# NHK2016mother_rev4.net
KiCad netlist of a schematic drawn in EAGLE
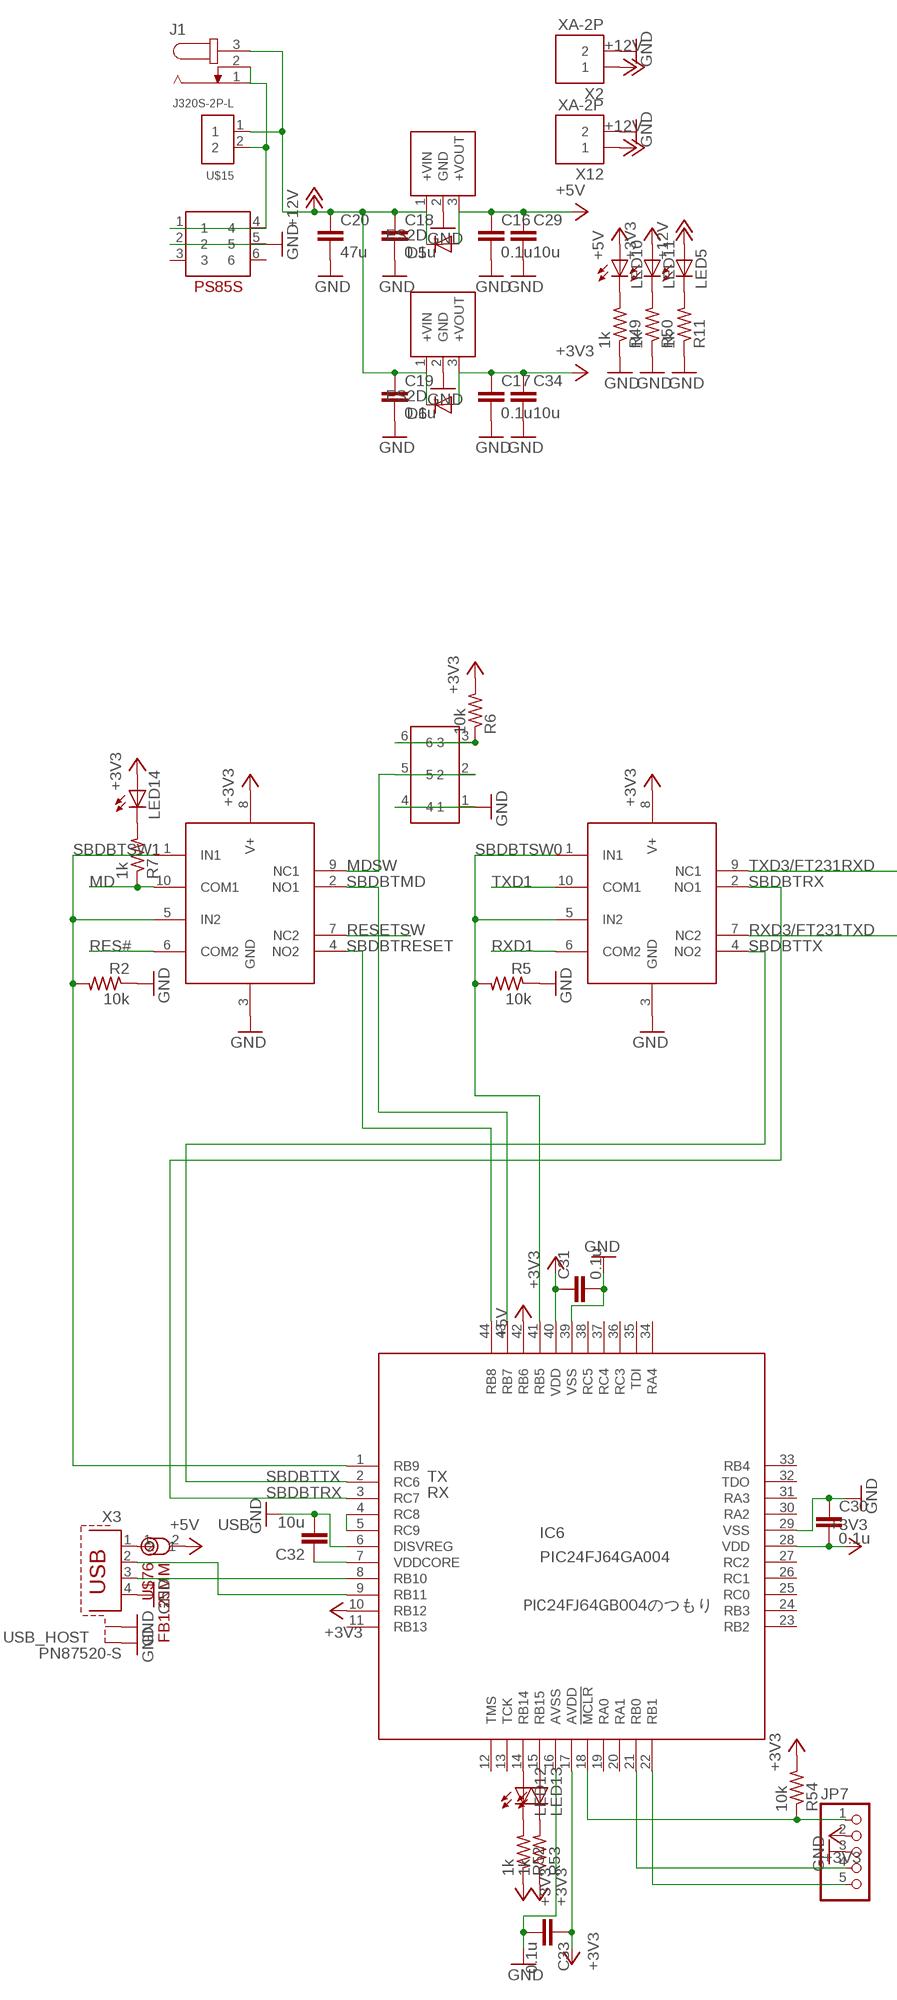
[diagram p0: schematic, sheet 1, part 1 of 2]
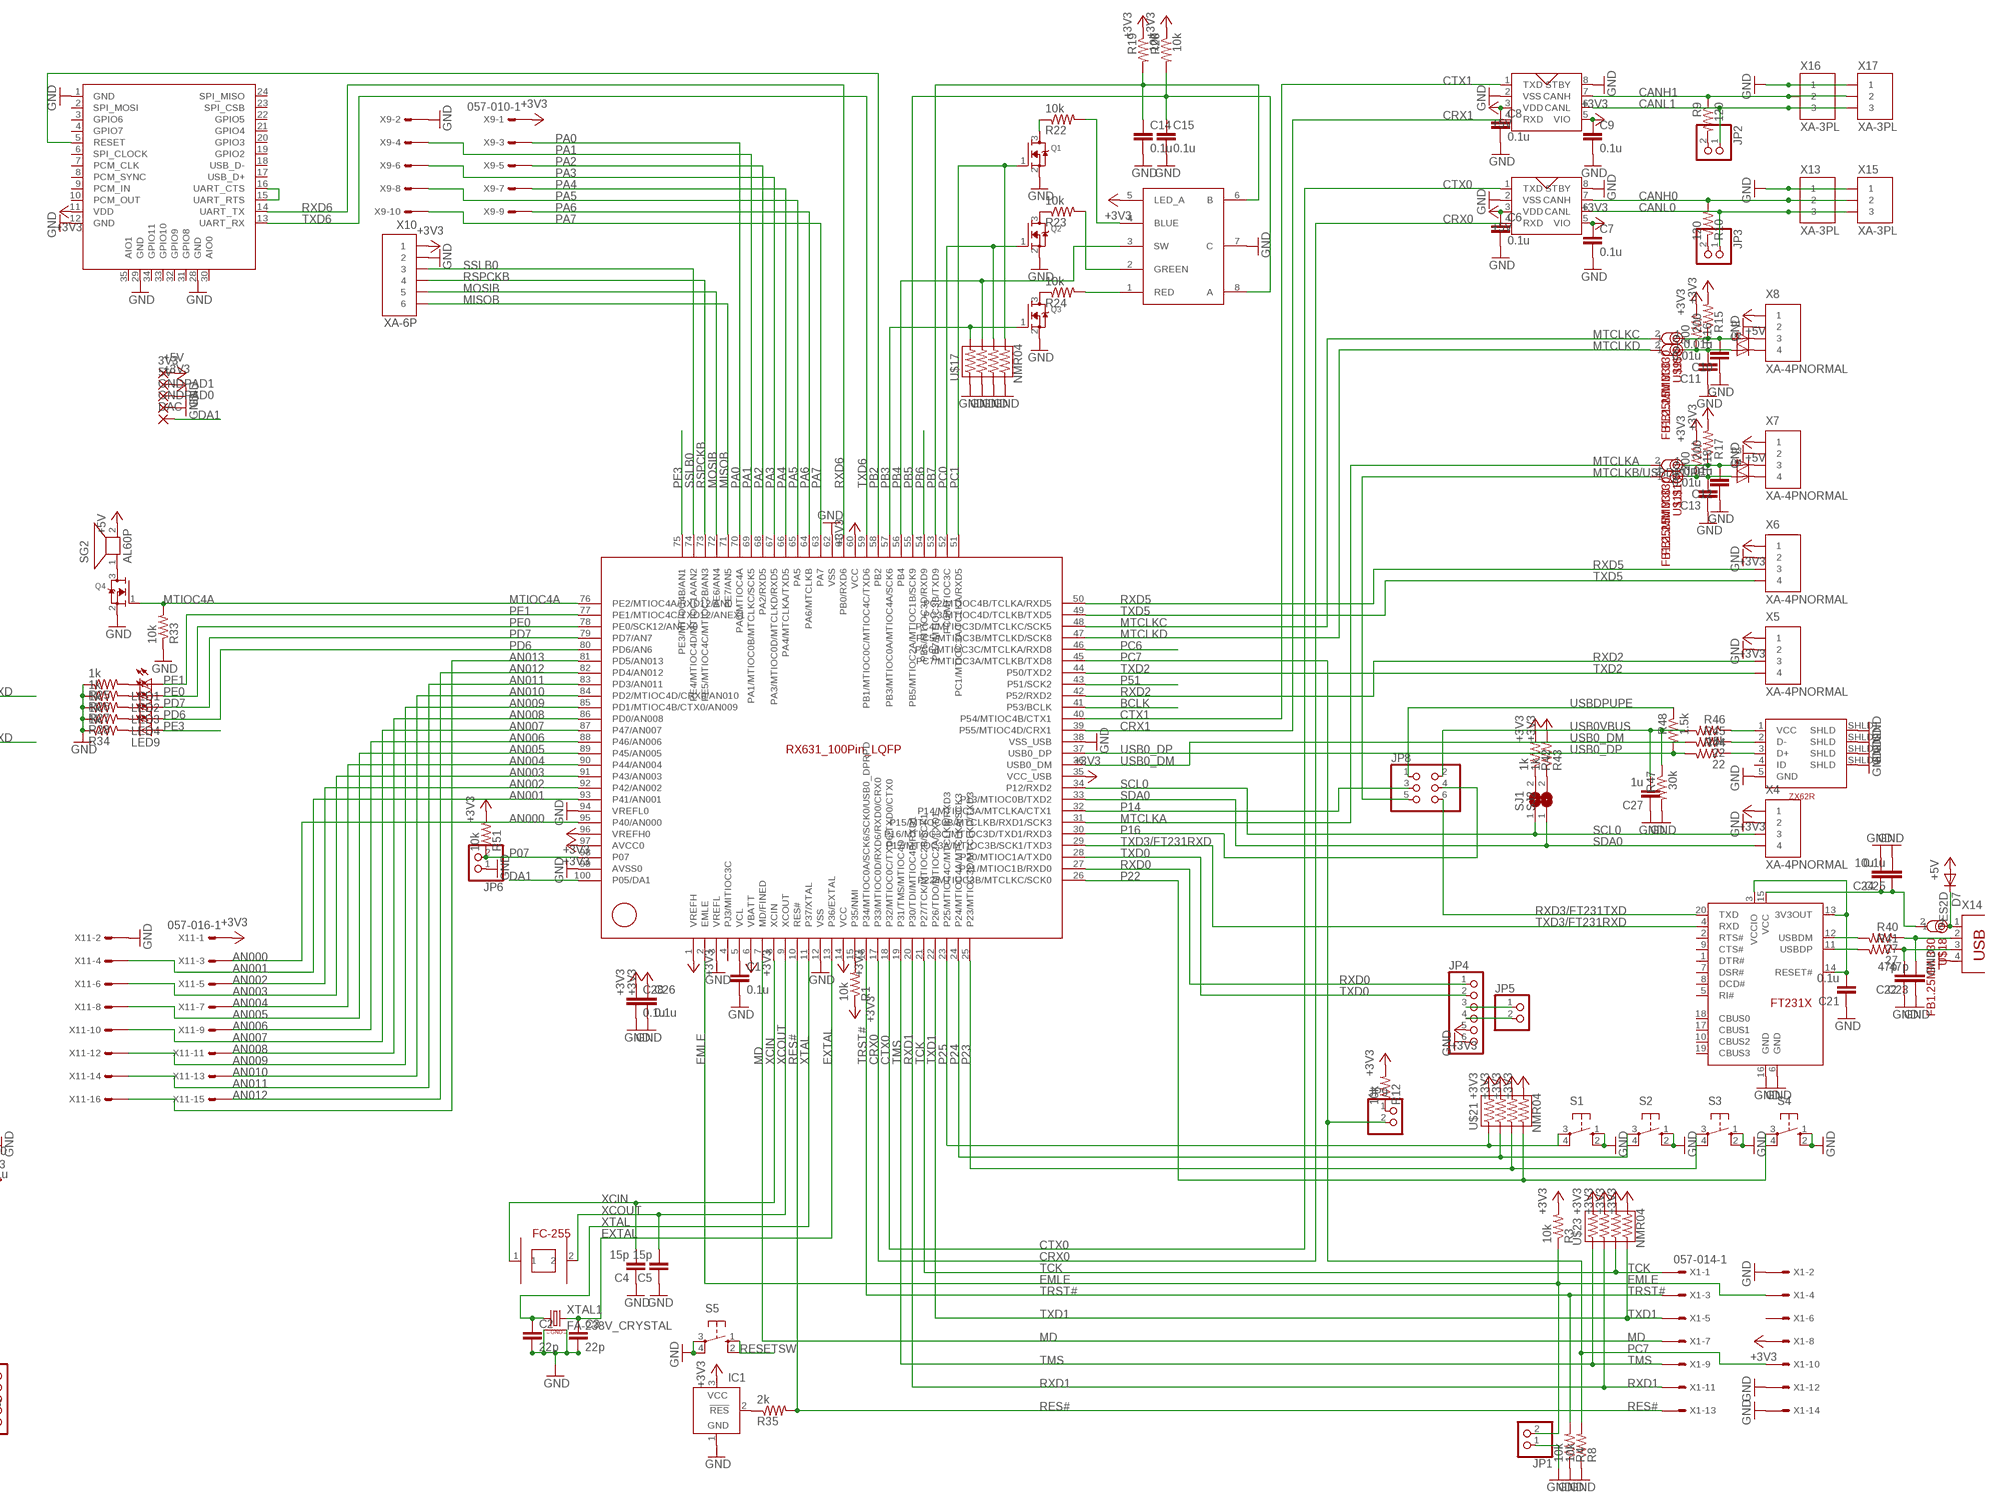
[diagram p1: schematic, sheet 1, part 2 of 2]

(export (version "E")
  (design (tool "Eeschema 10.0.6"))
  (components
    (comp (ref "3V3")
      (value "1,6/0,8")
      (footprint "eagle-import:1,6_0,8")
      (libsource (lib "eagle-import") (part "1,6/0,8"))
    )
    (comp (ref "5V")
      (value "1,6/0,8")
      (footprint "eagle-import:1,6_0,8")
      (libsource (lib "eagle-import") (part "1,6/0,8"))
    )
    (comp (ref "C1")
      (value "0.1u")
      (footprint "eagle-import:C0603K")
      (libsource (lib "eagle-import") (part "C-EUC0603K"))
    )
    (comp (ref "C2")
      (value "22p")
      (footprint "eagle-import:C2012")
      (libsource (lib "eagle-import") (part "C-EUC2012"))
    )
    (comp (ref "C3")
      (value "22p")
      (footprint "eagle-import:C2012")
      (libsource (lib "eagle-import") (part "C-EUC2012"))
    )
    (comp (ref "C4")
      (value "15p")
      (footprint "eagle-import:C0603K")
      (libsource (lib "eagle-import") (part "C-EUC0603K"))
    )
    (comp (ref "C5")
      (value "15p")
      (footprint "eagle-import:C0603K")
      (libsource (lib "eagle-import") (part "C-EUC0603K"))
    )
    (comp (ref "C6")
      (value "0.1u")
      (footprint "eagle-import:C0603K")
      (libsource (lib "eagle-import") (part "C-EUC0603K"))
    )
    (comp (ref "C7")
      (value "0.1u")
      (footprint "eagle-import:C0603K")
      (libsource (lib "eagle-import") (part "C-EUC0603K"))
    )
    (comp (ref "C8")
      (value "0.1u")
      (footprint "eagle-import:C0603K")
      (libsource (lib "eagle-import") (part "C-EUC0603K"))
    )
    (comp (ref "C9")
      (value "0.1u")
      (footprint "eagle-import:C0603K")
      (libsource (lib "eagle-import") (part "C-EUC0603K"))
    )
    (comp (ref "C10")
      (value "0.01u")
      (footprint "eagle-import:C0603K")
      (libsource (lib "eagle-import") (part "C-EUC0603K"))
    )
    (comp (ref "C11")
      (value "0.01u")
      (footprint "eagle-import:C0603K")
      (libsource (lib "eagle-import") (part "C-EUC0603K"))
    )
    (comp (ref "C12")
      (value "0.01u")
      (footprint "eagle-import:C0603K")
      (libsource (lib "eagle-import") (part "C-EUC0603K"))
    )
    (comp (ref "C13")
      (value "0.01u")
      (footprint "eagle-import:C0603K")
      (libsource (lib "eagle-import") (part "C-EUC0603K"))
    )
    (comp (ref "C14")
      (value "0.1u")
      (footprint "eagle-import:C0603K")
      (libsource (lib "eagle-import") (part "C-EUC0603K"))
    )
    (comp (ref "C15")
      (value "0.1u")
      (footprint "eagle-import:C0603K")
      (libsource (lib "eagle-import") (part "C-EUC0603K"))
    )
    (comp (ref "C16")
      (value "0.1u")
      (footprint "eagle-import:C0603K")
      (libsource (lib "eagle-import") (part "C-EUC0603K"))
    )
    (comp (ref "C17")
      (value "0.1u")
      (footprint "eagle-import:C0603K")
      (libsource (lib "eagle-import") (part "C-EUC0603K"))
    )
    (comp (ref "C18")
      (value "0.1u")
      (footprint "eagle-import:C0603K")
      (libsource (lib "eagle-import") (part "C-EUC0603K"))
    )
    (comp (ref "C19")
      (value "0.1u")
      (footprint "eagle-import:C0603K")
      (libsource (lib "eagle-import") (part "C-EUC0603K"))
    )
    (comp (ref "C20")
      (value "47u")
      (footprint "eagle-import:C3225")
      (libsource (lib "eagle-import") (part "C-EUC3225"))
    )
    (comp (ref "C21")
      (value "0.1u")
      (footprint "eagle-import:C0603K")
      (libsource (lib "eagle-import") (part "C-EUC0603K"))
    )
    (comp (ref "C22")
      (value "47p")
      (footprint "eagle-import:C0603K")
      (libsource (lib "eagle-import") (part "C-EUC0603K"))
    )
    (comp (ref "C23")
      (value "47p")
      (footprint "eagle-import:C0603K")
      (libsource (lib "eagle-import") (part "C-EUC0603K"))
    )
    (comp (ref "C24")
      (value "10u")
      (footprint "eagle-import:C1608")
      (libsource (lib "eagle-import") (part "C-EUC1608"))
    )
    (comp (ref "C25")
      (value "0.1u")
      (footprint "eagle-import:C0603K")
      (libsource (lib "eagle-import") (part "C-EUC0603K"))
    )
    (comp (ref "C26")
      (value "0.1u")
      (footprint "eagle-import:C0603K")
      (libsource (lib "eagle-import") (part "C-EUC0603K"))
    )
    (comp (ref "C27")
      (value "1u")
      (footprint "eagle-import:C0603K")
      (libsource (lib "eagle-import") (part "C-EUC0603K"))
    )
    (comp (ref "C28")
      (value "0.1u")
      (footprint "eagle-import:C0603K")
      (libsource (lib "eagle-import") (part "C-EUC0603K"))
    )
    (comp (ref "C29")
      (value "10u")
      (footprint "eagle-import:C1608")
      (libsource (lib "eagle-import") (part "C-EUC1608"))
    )
    (comp (ref "C30")
      (value "0.1u")
      (footprint "eagle-import:C0603K")
      (libsource (lib "eagle-import") (part "C-EUC0603K"))
    )
    (comp (ref "C31")
      (value "0.1u")
      (footprint "eagle-import:C0603K")
      (libsource (lib "eagle-import") (part "C-EUC0603K"))
    )
    (comp (ref "C32")
      (value "10u")
      (footprint "eagle-import:C1608")
      (libsource (lib "eagle-import") (part "C-EUC1608"))
    )
    (comp (ref "C33")
      (value "0.1u")
      (footprint "eagle-import:C0603K")
      (libsource (lib "eagle-import") (part "C-EUC0603K"))
    )
    (comp (ref "C34")
      (value "10u")
      (footprint "eagle-import:C1608")
      (libsource (lib "eagle-import") (part "C-EUC1608"))
    )
    (comp (ref "D1")
      (value "DIODESOD-523")
      (footprint "eagle-import:SOD-523")
      (libsource (lib "eagle-import") (part "DIODESOD-523"))
    )
    (comp (ref "D2")
      (value "DIODESOD-523")
      (footprint "eagle-import:SOD-523")
      (libsource (lib "eagle-import") (part "DIODESOD-523"))
    )
    (comp (ref "D3")
      (value "DIODESOD-523")
      (footprint "eagle-import:SOD-523")
      (libsource (lib "eagle-import") (part "DIODESOD-523"))
    )
    (comp (ref "D4")
      (value "DIODESOD-523")
      (footprint "eagle-import:SOD-523")
      (libsource (lib "eagle-import") (part "DIODESOD-523"))
    )
    (comp (ref "D5")
      (value "ES2D")
      (footprint "eagle-import:SMB")
      (libsource (lib "eagle-import") (part "ES2D"))
    )
    (comp (ref "D6")
      (value "ES2D")
      (footprint "eagle-import:SMB")
      (libsource (lib "eagle-import") (part "ES2D"))
    )
    (comp (ref "D7")
      (value "ES2D")
      (footprint "eagle-import:SMB")
      (libsource (lib "eagle-import") (part "ES2D"))
    )
    (comp (ref "DAC")
      (value "1,6/0,8")
      (footprint "eagle-import:1,6_0,8")
      (libsource (lib "eagle-import") (part "1,6/0,8"))
    )
    (comp (ref "FT231XS")
      (value "FT231X")
      (footprint "eagle-import:SSOP20")
      (libsource (lib "eagle-import") (part "FT231X"))
    )
    (comp (ref "GNDPAD0")
      (value "1,6/0,8")
      (footprint "eagle-import:1,6_0,8")
      (libsource (lib "eagle-import") (part "1,6/0,8"))
    )
    (comp (ref "GNDPAD1")
      (value "1,6/0,8")
      (footprint "eagle-import:1,6_0,8")
      (libsource (lib "eagle-import") (part "1,6/0,8"))
    )
    (comp (ref "IC1")
      (value "TCM809")
      (footprint "eagle-import:SOT23B-3")
      (fields (field (name "MF") "MICROCHIP") (field (name "MPN") "TCM809MENB713"))
      (libsource (lib "eagle-import") (part "TCM809"))
    )
    (comp (ref "IC6")
      (value "PIC24FJ64GA004")
      (footprint "eagle-import:TQFP44")
      (fields (field (name "MPN") "PIC24FJ64GA004-E/PT"))
      (libsource (lib "eagle-import") (part "PIC24FJ64GA004"))
    )
    (comp (ref "J1")
      (value "JACK-PLUG1")
      (footprint "eagle-import:SPC4078")
      (libsource (lib "eagle-import") (part "JACK-PLUG1"))
    )
    (comp (ref "JP1")
      (value "PINHD-1X2")
      (footprint "eagle-import:1X02")
      (libsource (lib "eagle-import") (part "PINHD-1X2"))
    )
    (comp (ref "JP2")
      (value "PINHD-1X2")
      (footprint "eagle-import:1X02")
      (libsource (lib "eagle-import") (part "PINHD-1X2"))
    )
    (comp (ref "JP3")
      (value "PINHD-1X2")
      (footprint "eagle-import:1X02")
      (libsource (lib "eagle-import") (part "PINHD-1X2"))
    )
    (comp (ref "JP4")
      (value "PINHD-1X6")
      (footprint "eagle-import:1X06")
      (libsource (lib "eagle-import") (part "PINHD-1X6"))
    )
    (comp (ref "JP5")
      (value "PINHD-1X2")
      (footprint "eagle-import:1X02")
      (libsource (lib "eagle-import") (part "PINHD-1X2"))
    )
    (comp (ref "JP6")
      (value "PINHD-1X2")
      (footprint "eagle-import:1X02")
      (libsource (lib "eagle-import") (part "PINHD-1X2"))
    )
    (comp (ref "JP7")
      (value "PINHD-1X5")
      (footprint "eagle-import:1X05")
      (libsource (lib "eagle-import") (part "PINHD-1X5"))
    )
    (comp (ref "JP8")
      (value "PINHD-2X3")
      (footprint "eagle-import:2X03")
      (libsource (lib "eagle-import") (part "PINHD-2X3"))
    )
    (comp (ref "JP9")
      (value "PINHD-1X2")
      (footprint "eagle-import:1X02")
      (libsource (lib "eagle-import") (part "PINHD-1X2"))
    )
    (comp (ref "LED1")
      (value "LEDSML0805")
      (footprint "eagle-import:SML0805")
      (libsource (lib "eagle-import") (part "LEDSML0805"))
    )
    (comp (ref "LED2")
      (value "LEDSML0805")
      (footprint "eagle-import:SML0805")
      (libsource (lib "eagle-import") (part "LEDSML0805"))
    )
    (comp (ref "LED3")
      (value "LEDSML0805")
      (footprint "eagle-import:SML0805")
      (libsource (lib "eagle-import") (part "LEDSML0805"))
    )
    (comp (ref "LED4")
      (value "LEDSML0805")
      (footprint "eagle-import:SML0805")
      (libsource (lib "eagle-import") (part "LEDSML0805"))
    )
    (comp (ref "LED5")
      (value "LEDSML0805")
      (footprint "eagle-import:SML0805")
      (libsource (lib "eagle-import") (part "LEDSML0805"))
    )
    (comp (ref "LED9")
      (value "LEDSML0805")
      (footprint "eagle-import:SML0805")
      (libsource (lib "eagle-import") (part "LEDSML0805"))
    )
    (comp (ref "LED10")
      (value "LEDSML0805")
      (footprint "eagle-import:SML0805")
      (libsource (lib "eagle-import") (part "LEDSML0805"))
    )
    (comp (ref "LED11")
      (value "LEDSML0805")
      (footprint "eagle-import:SML0805")
      (libsource (lib "eagle-import") (part "LEDSML0805"))
    )
    (comp (ref "LED12")
      (value "LEDSML0805")
      (footprint "eagle-import:SML0805")
      (libsource (lib "eagle-import") (part "LEDSML0805"))
    )
    (comp (ref "LED13")
      (value "LEDSML0805")
      (footprint "eagle-import:SML0805")
      (libsource (lib "eagle-import") (part "LEDSML0805"))
    )
    (comp (ref "LED14")
      (value "LEDSML0805")
      (footprint "eagle-import:SML0805")
      (libsource (lib "eagle-import") (part "LEDSML0805"))
    )
    (comp (ref "Q1")
      (value "MOSFET-NREFLOW")
      (footprint "eagle-import:SOT23")
      (libsource (lib "eagle-import") (part "MOSFET-NREFLOW"))
    )
    (comp (ref "Q2")
      (value "MOSFET-NREFLOW")
      (footprint "eagle-import:SOT23")
      (libsource (lib "eagle-import") (part "MOSFET-NREFLOW"))
    )
    (comp (ref "Q3")
      (value "MOSFET-NREFLOW")
      (footprint "eagle-import:SOT23")
      (libsource (lib "eagle-import") (part "MOSFET-NREFLOW"))
    )
    (comp (ref "Q4")
      (value "MOSFET-NREFLOW")
      (footprint "eagle-import:SOT23")
      (libsource (lib "eagle-import") (part "MOSFET-NREFLOW"))
    )
    (comp (ref "R1")
      (value "10k")
      (footprint "eagle-import:MINI_MELF-0102W")
      (libsource (lib "eagle-import") (part "R-US_MELF0102W"))
    )
    (comp (ref "R2")
      (value "10k")
      (footprint "eagle-import:MINI_MELF-0102W")
      (libsource (lib "eagle-import") (part "R-US_MELF0102W"))
    )
    (comp (ref "R3")
      (value "10k")
      (footprint "eagle-import:MINI_MELF-0102W")
      (libsource (lib "eagle-import") (part "R-US_MELF0102W"))
    )
    (comp (ref "R4")
      (value "10k")
      (footprint "eagle-import:MINI_MELF-0102W")
      (libsource (lib "eagle-import") (part "R-US_MELF0102W"))
    )
    (comp (ref "R5")
      (value "10k")
      (footprint "eagle-import:MINI_MELF-0102W")
      (libsource (lib "eagle-import") (part "R-US_MELF0102W"))
    )
    (comp (ref "R6")
      (value "10k")
      (footprint "eagle-import:MINI_MELF-0102W")
      (libsource (lib "eagle-import") (part "R-US_MELF0102W"))
    )
    (comp (ref "R7")
      (value "1k")
      (footprint "eagle-import:MINI_MELF-0102W")
      (libsource (lib "eagle-import") (part "R-US_MELF0102W"))
    )
    (comp (ref "R8")
      (value "10k")
      (footprint "eagle-import:MINI_MELF-0102W")
      (libsource (lib "eagle-import") (part "R-US_MELF0102W"))
    )
    (comp (ref "R9")
      (value "120")
      (footprint "eagle-import:MINI_MELF-0102W")
      (libsource (lib "eagle-import") (part "R-US_MELF0102W"))
    )
    (comp (ref "R10")
      (value "120")
      (footprint "eagle-import:MINI_MELF-0102W")
      (libsource (lib "eagle-import") (part "R-US_MELF0102W"))
    )
    (comp (ref "R11")
      (value "1k")
      (footprint "eagle-import:MINI_MELF-0102W")
      (libsource (lib "eagle-import") (part "R-US_MELF0102W"))
    )
    (comp (ref "R12")
      (value "10k")
      (footprint "eagle-import:MINI_MELF-0102W")
      (libsource (lib "eagle-import") (part "R-US_MELF0102W"))
    )
    (comp (ref "R15")
      (value "200")
      (footprint "eagle-import:MINI_MELF-0102W")
      (libsource (lib "eagle-import") (part "R-US_MELF0102W"))
    )
    (comp (ref "R16")
      (value "200")
      (footprint "eagle-import:MINI_MELF-0102W")
      (libsource (lib "eagle-import") (part "R-US_MELF0102W"))
    )
    (comp (ref "R17")
      (value "200")
      (footprint "eagle-import:MINI_MELF-0102W")
      (libsource (lib "eagle-import") (part "R-US_MELF0102W"))
    )
    (comp (ref "R18")
      (value "200")
      (footprint "eagle-import:MINI_MELF-0102W")
      (libsource (lib "eagle-import") (part "R-US_MELF0102W"))
    )
    (comp (ref "R19")
      (value "10k")
      (footprint "eagle-import:MINI_MELF-0102W")
      (libsource (lib "eagle-import") (part "R-US_MELF0102W"))
    )
    (comp (ref "R20")
      (value "10k")
      (footprint "eagle-import:MINI_MELF-0102W")
      (libsource (lib "eagle-import") (part "R-US_MELF0102W"))
    )
    (comp (ref "R22")
      (value "10k")
      (footprint "eagle-import:MINI_MELF-0102W")
      (libsource (lib "eagle-import") (part "R-US_MELF0102W"))
    )
    (comp (ref "R23")
      (value "10k")
      (footprint "eagle-import:MINI_MELF-0102W")
      (libsource (lib "eagle-import") (part "R-US_MELF0102W"))
    )
    (comp (ref "R24")
      (value "10k")
      (footprint "eagle-import:MINI_MELF-0102W")
      (libsource (lib "eagle-import") (part "R-US_MELF0102W"))
    )
    (comp (ref "R25")
      (value "1k")
      (footprint "eagle-import:MINI_MELF-0102W")
      (libsource (lib "eagle-import") (part "R-US_MELF0102W"))
    )
    (comp (ref "R26")
      (value "1k")
      (footprint "eagle-import:MINI_MELF-0102W")
      (libsource (lib "eagle-import") (part "R-US_MELF0102W"))
    )
    (comp (ref "R27")
      (value "1k")
      (footprint "eagle-import:MINI_MELF-0102W")
      (libsource (lib "eagle-import") (part "R-US_MELF0102W"))
    )
    (comp (ref "R28")
      (value "1k")
      (footprint "eagle-import:MINI_MELF-0102W")
      (libsource (lib "eagle-import") (part "R-US_MELF0102W"))
    )
    (comp (ref "R33")
      (value "10k")
      (footprint "eagle-import:MINI_MELF-0102W")
      (libsource (lib "eagle-import") (part "R-US_MELF0102W"))
    )
    (comp (ref "R34")
      (value "1k")
      (footprint "eagle-import:MINI_MELF-0102W")
      (libsource (lib "eagle-import") (part "R-US_MELF0102W"))
    )
    (comp (ref "R35")
      (value "2k")
      (footprint "eagle-import:MINI_MELF-0102W")
      (libsource (lib "eagle-import") (part "R-US_MELF0102W"))
    )
    (comp (ref "R40")
      (value "27")
      (footprint "eagle-import:MINI_MELF-0102W")
      (libsource (lib "eagle-import") (part "R-US_MELF0102W"))
    )
    (comp (ref "R41")
      (value "27")
      (footprint "eagle-import:MINI_MELF-0102W")
      (libsource (lib "eagle-import") (part "R-US_MELF0102W"))
    )
    (comp (ref "R42")
      (value "1k")
      (footprint "eagle-import:MINI_MELF-0102W")
      (libsource (lib "eagle-import") (part "R-US_MELF0102W"))
    )
    (comp (ref "R43")
      (value "1k")
      (footprint "eagle-import:MINI_MELF-0102W")
      (libsource (lib "eagle-import") (part "R-US_MELF0102W"))
    )
    (comp (ref "R44")
      (value "22")
      (footprint "eagle-import:MINI_MELF-0102W")
      (libsource (lib "eagle-import") (part "R-US_MELF0102W"))
    )
    (comp (ref "R45")
      (value "22")
      (footprint "eagle-import:MINI_MELF-0102W")
      (libsource (lib "eagle-import") (part "R-US_MELF0102W"))
    )
    (comp (ref "R46")
      (value "15k")
      (footprint "eagle-import:MINI_MELF-0102W")
      (libsource (lib "eagle-import") (part "R-US_MELF0102W"))
    )
    (comp (ref "R47")
      (value "30k")
      (footprint "eagle-import:MINI_MELF-0102W")
      (libsource (lib "eagle-import") (part "R-US_MELF0102W"))
    )
    (comp (ref "R48")
      (value "1.5k")
      (footprint "eagle-import:MINI_MELF-0102W")
      (libsource (lib "eagle-import") (part "R-US_MELF0102W"))
    )
    (comp (ref "R49")
      (value "1k")
      (footprint "eagle-import:MINI_MELF-0102W")
      (libsource (lib "eagle-import") (part "R-US_MELF0102W"))
    )
    (comp (ref "R50")
      (value "1k")
      (footprint "eagle-import:MINI_MELF-0102W")
      (libsource (lib "eagle-import") (part "R-US_MELF0102W"))
    )
    (comp (ref "R51")
      (value "10k")
      (footprint "eagle-import:MINI_MELF-0102W")
      (libsource (lib "eagle-import") (part "R-US_MELF0102W"))
    )
    (comp (ref "R52")
      (value "1k")
      (footprint "eagle-import:MINI_MELF-0102W")
      (libsource (lib "eagle-import") (part "R-US_MELF0102W"))
    )
    (comp (ref "R53")
      (value "1k")
      (footprint "eagle-import:MINI_MELF-0102W")
      (libsource (lib "eagle-import") (part "R-US_MELF0102W"))
    )
    (comp (ref "R54")
      (value "10k")
      (footprint "eagle-import:MINI_MELF-0102W")
      (libsource (lib "eagle-import") (part "R-US_MELF0102W"))
    )
    (comp (ref "S1")
      (value "10-XX")
      (footprint "eagle-import:B3F-10XX")
      (fields (field (name "MPN") "B3F-1000"))
      (libsource (lib "eagle-import") (part "10-XX"))
    )
    (comp (ref "S2")
      (value "10-XX")
      (footprint "eagle-import:B3F-10XX")
      (fields (field (name "MPN") "B3F-1000"))
      (libsource (lib "eagle-import") (part "10-XX"))
    )
    (comp (ref "S3")
      (value "10-XX")
      (footprint "eagle-import:B3F-10XX")
      (fields (field (name "MPN") "B3F-1000"))
      (libsource (lib "eagle-import") (part "10-XX"))
    )
    (comp (ref "S4")
      (value "10-XX")
      (footprint "eagle-import:B3F-10XX")
      (fields (field (name "MPN") "B3F-1000"))
      (libsource (lib "eagle-import") (part "10-XX"))
    )
    (comp (ref "S5")
      (value "10-XX")
      (footprint "eagle-import:B3F-10XX")
      (fields (field (name "MPN") "B3F-1000"))
      (libsource (lib "eagle-import") (part "10-XX"))
    )
    (comp (ref "SG2")
      (value "AL60P")
      (footprint "eagle-import:AL60P")
      (libsource (lib "eagle-import") (part "AL60P"))
    )
    (comp (ref "SJ1") (value "SJ") (footprint "eagle-import:SJ") (libsource (lib "eagle-import") (part "SJ")))
    (comp (ref "SJ2") (value "SJ") (footprint "eagle-import:SJ") (libsource (lib "eagle-import") (part "SJ")))
    (comp (ref "U$1")
      (value "R5F5631FDDFP")
      (footprint "eagle-import:LQFP100")
      (libsource (lib "eagle-import") (part "R5F5631FDDFP"))
    )
    (comp (ref "U$3")
      (value "FC-255")
      (footprint "eagle-import:FC-255")
      (libsource (lib "eagle-import") (part "FC-255"))
    )
    (comp (ref "U$4")
      (value "MCP2562")
      (footprint "eagle-import:MCP2562")
      (libsource (lib "eagle-import") (part "MCP2562"))
    )
    (comp (ref "U$5")
      (value "MCP2562")
      (footprint "eagle-import:MCP2562")
      (libsource (lib "eagle-import") (part "MCP2562"))
    )
    (comp (ref "U$8")
      (value "FB1.25MM 330")
      (footprint "eagle-import:2012")
      (libsource (lib "eagle-import") (part "FB1.25MM"))
    )
    (comp (ref "U$9")
      (value "FB1.25MM 330")
      (footprint "eagle-import:2012")
      (libsource (lib "eagle-import") (part "FB1.25MM"))
    )
    (comp (ref "U$10")
      (value "FB1.25MM 330")
      (footprint "eagle-import:2012")
      (libsource (lib "eagle-import") (part "FB1.25MM"))
    )
    (comp (ref "U$11")
      (value "FB1.25MM 330")
      (footprint "eagle-import:2012")
      (libsource (lib "eagle-import") (part "FB1.25MM"))
    )
    (comp (ref "U$12")
      (value "RN42")
      (footprint "eagle-import:RN42")
      (libsource (lib "eagle-import") (part "RN42"))
    )
    (comp (ref "U$13")
      (value "M78AR033-0.5")
      (footprint "eagle-import:M78AR033-0.5V")
      (libsource (lib "eagle-import") (part "M78AR033-0.5"))
    )
    (comp (ref "U$14")
      (value "M78AR033-0.5")
      (footprint "eagle-import:M78AR033-0.5V")
      (libsource (lib "eagle-import") (part "M78AR033-0.5"))
    )
    (comp (ref "U$15")
      (value "J320S-2P-L")
      (footprint "eagle-import:J320S-2P-L")
      (libsource (lib "eagle-import") (part "J320S-2P-L"))
    )
    (comp (ref "U$16")
      (value "PS-85S")
      (footprint "eagle-import:PS-85S")
      (libsource (lib "eagle-import") (part "PS-85S"))
    )
    (comp (ref "U$17")
      (value "NMR04")
      (footprint "eagle-import:MNR04")
      (libsource (lib "eagle-import") (part "NMR04"))
    )
    (comp (ref "U$18")
      (value "FB1.25MM 330")
      (footprint "eagle-import:2012")
      (libsource (lib "eagle-import") (part "FB1.25MM"))
    )
    (comp (ref "U$21")
      (value "NMR04")
      (footprint "eagle-import:MNR04")
      (libsource (lib "eagle-import") (part "NMR04"))
    )
    (comp (ref "U$22")
      (value "ZX62R")
      (footprint "eagle-import:ZX62R")
      (libsource (lib "eagle-import") (part "ZX62R"))
    )
    (comp (ref "U$23")
      (value "NMR04")
      (footprint "eagle-import:MNR04")
      (libsource (lib "eagle-import") (part "NMR04"))
    )
    (comp (ref "U$24")
      (value "MULTIPLEXER2CIR")
      (footprint "eagle-import:MULTIPLEXER2CIR")
      (libsource (lib "eagle-import") (part "MULTIPLEXER2CIR"))
    )
    (comp (ref "U$25")
      (value "MULTIPLEXER2CIR")
      (footprint "eagle-import:MULTIPLEXER2CIR")
      (libsource (lib "eagle-import") (part "MULTIPLEXER2CIR"))
    )
    (comp (ref "U$58")
      (value "EC12PLRGBSDVBF")
      (footprint "eagle-import:EC12PLRGBSDVBF")
      (libsource (lib "eagle-import") (part "EC12PLRGBSDVBF"))
    )
    (comp (ref "U$76")
      (value "FB1.25MM")
      (footprint "eagle-import:2012")
      (libsource (lib "eagle-import") (part "FB1.25MM"))
    )
    (comp (ref "U$82")
      (value "SSSS2")
      (footprint "eagle-import:SSSS2")
      (libsource (lib "eagle-import") (part "SSSS2"))
    )
    (comp (ref "X1")
      (value "057-014-1")
      (footprint "eagle-import:057-014-1")
      (libsource (lib "eagle-import") (part "057-014-1"))
    )
    (comp (ref "X2")
      (value "XA-2P")
      (footprint "eagle-import:XA-2P")
      (libsource (lib "eagle-import") (part "XA-2P"))
    )
    (comp (ref "X3")
      (value "PN87520-S")
      (footprint "eagle-import:PN87520-S")
      (libsource (lib "eagle-import") (part "PN87520-S"))
    )
    (comp (ref "X4")
      (value "XA-4PNORMAL")
      (footprint "eagle-import:XA-4P")
      (libsource (lib "eagle-import") (part "XA-4PNORMAL"))
    )
    (comp (ref "X5")
      (value "XA-4PNORMAL")
      (footprint "eagle-import:XA-4P")
      (libsource (lib "eagle-import") (part "XA-4PNORMAL"))
    )
    (comp (ref "X6")
      (value "XA-4PNORMAL")
      (footprint "eagle-import:XA-4P")
      (libsource (lib "eagle-import") (part "XA-4PNORMAL"))
    )
    (comp (ref "X7")
      (value "XA-4PNORMAL")
      (footprint "eagle-import:XA-4P")
      (libsource (lib "eagle-import") (part "XA-4PNORMAL"))
    )
    (comp (ref "X8")
      (value "XA-4PNORMAL")
      (footprint "eagle-import:XA-4P")
      (libsource (lib "eagle-import") (part "XA-4PNORMAL"))
    )
    (comp (ref "X9")
      (value "057-010-1")
      (footprint "eagle-import:057-010-1")
      (libsource (lib "eagle-import") (part "057-010-1"))
    )
    (comp (ref "X10")
      (value "XA-6P")
      (footprint "eagle-import:XA-6P")
      (libsource (lib "eagle-import") (part "XA-6P"))
    )
    (comp (ref "X11")
      (value "057-016-1")
      (footprint "eagle-import:057-016-1")
      (libsource (lib "eagle-import") (part "057-016-1"))
    )
    (comp (ref "X12")
      (value "XA-2P")
      (footprint "eagle-import:XA-2P")
      (libsource (lib "eagle-import") (part "XA-2P"))
    )
    (comp (ref "X13")
      (value "XA-3PL")
      (footprint "eagle-import:XA-3P-L")
      (libsource (lib "eagle-import") (part "XA-3PL"))
    )
    (comp (ref "X14")
      (value "PN61729")
      (footprint "eagle-import:PN61729")
      (fields (field (name "OC_FARNELL") "unknown") (field (name "OC_NEWARK") "unknown"))
      (libsource (lib "eagle-import") (part "PN61729"))
    )
    (comp (ref "X15")
      (value "XA-3PL")
      (footprint "eagle-import:XA-3P-L")
      (libsource (lib "eagle-import") (part "XA-3PL"))
    )
    (comp (ref "X16")
      (value "XA-3PL")
      (footprint "eagle-import:XA-3P-L")
      (libsource (lib "eagle-import") (part "XA-3PL"))
    )
    (comp (ref "X17")
      (value "XA-3PL")
      (footprint "eagle-import:XA-3P-L")
      (libsource (lib "eagle-import") (part "XA-3PL"))
    )
    (comp (ref "XTAL1")
      (value "FA-238V_CRYSTAL")
      (footprint "eagle-import:FA-238V_CRYSTAL")
      (libsource (lib "eagle-import") (part "FA-238V_CRYSTAL"))
    )
  )
  (nets
    (net (code "1") (name "+3V3") (class "Default")
      (node (ref "5V") (pin "1") (pinfunction "P_1") (pintype "passive"))
      (node (ref "C17") (pin "1") (pinfunction "1_1") (pintype "passive"))
      (node (ref "C26") (pin "1") (pinfunction "1_1") (pintype "passive"))
      (node (ref "C28") (pin "1") (pinfunction "1_1") (pintype "passive"))
      (node (ref "C30") (pin "2") (pinfunction "2_2") (pintype "passive"))
      (node (ref "C31") (pin "1") (pinfunction "1_1") (pintype "passive"))
      (node (ref "C33") (pin "1") (pinfunction "1_1") (pintype "passive"))
      (node (ref "C34") (pin "1") (pinfunction "1_1") (pintype "passive"))
      (node (ref "C7") (pin "1") (pinfunction "1_1") (pintype "passive"))
      (node (ref "C9") (pin "1") (pinfunction "1_1") (pintype "passive"))
      (node (ref "D6") (pin "A") (pinfunction "A_A") (pintype "passive"))
      (node (ref "IC1") (pin "3") (pinfunction "VCC_3") (pintype "power_in"))
      (node (ref "IC6") (pin "10") (pinfunction "RB12_10") (pintype "bidirectional"))
      (node (ref "IC6") (pin "17") (pinfunction "AVDD_17") (pintype "power_in"))
      (node (ref "IC6") (pin "28") (pinfunction "VDD_28") (pintype "power_in"))
      (node (ref "IC6") (pin "40") (pinfunction "VDD_40") (pintype "power_in"))
      (node (ref "JP4") (pin "5") (pinfunction "5_5") (pintype "passive"))
      (node (ref "JP7") (pin "2") (pinfunction "2_2") (pintype "passive"))
      (node (ref "LED11") (pin "A") (pinfunction "A_A") (pintype "passive"))
      (node (ref "LED14") (pin "A") (pinfunction "A_A") (pintype "passive"))
      (node (ref "R1") (pin "1") (pinfunction "1_1") (pintype "passive"))
      (node (ref "R12") (pin "2") (pinfunction "2_2") (pintype "passive"))
      (node (ref "R15") (pin "2") (pinfunction "2_2") (pintype "passive"))
      (node (ref "R16") (pin "2") (pinfunction "2_2") (pintype "passive"))
      (node (ref "R17") (pin "2") (pinfunction "2_2") (pintype "passive"))
      (node (ref "R18") (pin "2") (pinfunction "2_2") (pintype "passive"))
      (node (ref "R19") (pin "1") (pinfunction "1_1") (pintype "passive"))
      (node (ref "R20") (pin "1") (pinfunction "1_1") (pintype "passive"))
      (node (ref "R3") (pin "2") (pinfunction "2_2") (pintype "passive"))
      (node (ref "R42") (pin "2") (pinfunction "2_2") (pintype "passive"))
      (node (ref "R43") (pin "2") (pinfunction "2_2") (pintype "passive"))
      (node (ref "R51") (pin "2") (pinfunction "2_2") (pintype "passive"))
      (node (ref "R52") (pin "1") (pinfunction "1_1") (pintype "passive"))
      (node (ref "R53") (pin "1") (pinfunction "1_1") (pintype "passive"))
      (node (ref "R54") (pin "2") (pinfunction "2_2") (pintype "passive"))
      (node (ref "R6") (pin "2") (pinfunction "2_2") (pintype "passive"))
      (node (ref "U$1") (pin "1") (pinfunction "VREFH_1") (pintype "bidirectional"))
      (node (ref "U$1") (pin "14") (pinfunction "VCC_14") (pintype "bidirectional"))
      (node (ref "U$1") (pin "35") (pinfunction "VCC_USB_35") (pintype "bidirectional"))
      (node (ref "U$1") (pin "6") (pinfunction "VBATT_6") (pintype "bidirectional"))
      (node (ref "U$1") (pin "60") (pinfunction "VCC_60") (pintype "bidirectional"))
      (node (ref "U$1") (pin "96") (pinfunction "VREFH0_96") (pintype "bidirectional"))
      (node (ref "U$1") (pin "97") (pinfunction "AVCC0_97") (pintype "bidirectional"))
      (node (ref "U$12") (pin "11") (pinfunction "VDD_11") (pintype "power_in"))
      (node (ref "U$14") (pin "3") (pinfunction "+VOUT_3") (pintype "power_in"))
      (node (ref "U$21") (pin "2") (pinfunction "2_2") (pintype "passive"))
      (node (ref "U$21") (pin "4") (pinfunction "4_4") (pintype "passive"))
      (node (ref "U$21") (pin "6") (pinfunction "6_6") (pintype "passive"))
      (node (ref "U$21") (pin "8") (pinfunction "8_8") (pintype "passive"))
      (node (ref "U$23") (pin "2") (pinfunction "2_2") (pintype "passive"))
      (node (ref "U$23") (pin "4") (pinfunction "4_4") (pintype "passive"))
      (node (ref "U$23") (pin "6") (pinfunction "6_6") (pintype "passive"))
      (node (ref "U$23") (pin "8") (pinfunction "8_8") (pintype "passive"))
      (node (ref "U$24") (pin "8") (pinfunction "V+_8") (pintype "bidirectional"))
      (node (ref "U$25") (pin "8") (pinfunction "V+_8") (pintype "bidirectional"))
      (node (ref "U$4") (pin "5") (pinfunction "VIO_5") (pintype "power_in"))
      (node (ref "U$5") (pin "5") (pinfunction "VIO_5") (pintype "power_in"))
      (node (ref "U$58") (pin "5") (pinfunction "LED_A_5") (pintype "bidirectional"))
      (node (ref "X1") (pin "8") (pinfunction "S_8") (pintype "passive"))
      (node (ref "X10") (pin "1") (pinfunction "1_1") (pintype "bidirectional"))
      (node (ref "X11") (pin "1") (pinfunction "S_1") (pintype "passive"))
      (node (ref "X4") (pin "1") (pinfunction "1_1") (pintype "bidirectional"))
      (node (ref "X5") (pin "1") (pinfunction "1_1") (pintype "bidirectional"))
      (node (ref "X6") (pin "1") (pinfunction "1_1") (pintype "bidirectional"))
      (node (ref "X9") (pin "1") (pinfunction "S_1") (pintype "passive"))
    )
    (net (code "2") (name "+5V") (class "Default")
      (node (ref "3V3") (pin "1") (pinfunction "P_1") (pintype "passive"))
      (node (ref "C16") (pin "1") (pinfunction "1_1") (pintype "passive"))
      (node (ref "C29") (pin "1") (pinfunction "1_1") (pintype "passive"))
      (node (ref "C6") (pin "1") (pinfunction "1_1") (pintype "passive"))
      (node (ref "C8") (pin "1") (pinfunction "1_1") (pintype "passive"))
      (node (ref "D5") (pin "A") (pinfunction "A_A") (pintype "passive"))
      (node (ref "D7") (pin "A") (pinfunction "A_A") (pintype "passive"))
      (node (ref "IC6") (pin "42") (pinfunction "RB6_42") (pintype "bidirectional"))
      (node (ref "LED10") (pin "A") (pinfunction "A_A") (pintype "passive"))
      (node (ref "SG2") (pin "2") (pinfunction "2_2") (pintype "passive"))
      (node (ref "U$13") (pin "3") (pinfunction "+VOUT_3") (pintype "power_in"))
      (node (ref "U$4") (pin "3") (pinfunction "VDD_3") (pintype "power_in"))
      (node (ref "U$5") (pin "3") (pinfunction "VDD_3") (pintype "power_in"))
      (node (ref "U$76") (pin "2") (pinfunction "2_2") (pintype "passive"))
      (node (ref "X7") (pin "1") (pinfunction "1_1") (pintype "bidirectional"))
      (node (ref "X8") (pin "1") (pinfunction "1_1") (pintype "bidirectional"))
    )
    (net (code "3") (name "+12V") (class "Default")
      (node (ref "C18") (pin "1") (pinfunction "1_1") (pintype "passive"))
      (node (ref "C19") (pin "1") (pinfunction "1_1") (pintype "passive"))
      (node (ref "C20") (pin "1") (pinfunction "1_1") (pintype "passive"))
      (node (ref "D5") (pin "C") (pinfunction "C_C") (pintype "passive"))
      (node (ref "D6") (pin "C") (pinfunction "C_C") (pintype "passive"))
      (node (ref "J1") (pin "3") (pinfunction "3_3") (pintype "passive"))
      (node (ref "LED5") (pin "A") (pinfunction "A_A") (pintype "passive"))
      (node (ref "U$13") (pin "1") (pinfunction "+VIN_1") (pintype "power_in"))
      (node (ref "U$14") (pin "1") (pinfunction "+VIN_1") (pintype "power_in"))
      (node (ref "U$15") (pin "1") (pinfunction "1_1") (pintype "bidirectional"))
      (node (ref "X12") (pin "1") (pinfunction "1_1") (pintype "bidirectional"))
      (node (ref "X2") (pin "1") (pinfunction "1_1") (pintype "bidirectional"))
    )
    (net (code "4") (name "/AN000") (class "Default")
      (node (ref "U$1") (pin "95") (pinfunction "P40/AN000_95") (pintype "bidirectional"))
      (node (ref "X11") (pin "3") (pinfunction "S_3") (pintype "passive"))
    )
    (net (code "5") (name "/AN001") (class "Default")
      (node (ref "U$1") (pin "93") (pinfunction "P41/AN001_93") (pintype "bidirectional"))
      (node (ref "X11") (pin "4") (pinfunction "S_4") (pintype "passive"))
    )
    (net (code "6") (name "/AN002") (class "Default")
      (node (ref "U$1") (pin "92") (pinfunction "P42/AN002_92") (pintype "bidirectional"))
      (node (ref "X11") (pin "5") (pinfunction "S_5") (pintype "passive"))
    )
    (net (code "7") (name "/AN003") (class "Default")
      (node (ref "U$1") (pin "91") (pinfunction "P43/AN003_91") (pintype "bidirectional"))
      (node (ref "X11") (pin "6") (pinfunction "S_6") (pintype "passive"))
    )
    (net (code "8") (name "/AN004") (class "Default")
      (node (ref "U$1") (pin "90") (pinfunction "P44/AN004_90") (pintype "bidirectional"))
      (node (ref "X11") (pin "7") (pinfunction "S_7") (pintype "passive"))
    )
    (net (code "9") (name "/AN005") (class "Default")
      (node (ref "U$1") (pin "89") (pinfunction "P45/AN005_89") (pintype "bidirectional"))
      (node (ref "X11") (pin "8") (pinfunction "S_8") (pintype "passive"))
    )
    (net (code "10") (name "/AN006") (class "Default")
      (node (ref "U$1") (pin "88") (pinfunction "P46/AN006_88") (pintype "bidirectional"))
      (node (ref "X11") (pin "9") (pinfunction "S_9") (pintype "passive"))
    )
    (net (code "11") (name "/AN007") (class "Default")
      (node (ref "U$1") (pin "87") (pinfunction "P47/AN007_87") (pintype "bidirectional"))
      (node (ref "X11") (pin "10") (pinfunction "S_10") (pintype "passive"))
    )
    (net (code "12") (name "/AN008") (class "Default")
      (node (ref "U$1") (pin "86") (pinfunction "PD0/AN008_86") (pintype "bidirectional"))
      (node (ref "X11") (pin "11") (pinfunction "S_11") (pintype "passive"))
    )
    (net (code "13") (name "/AN009") (class "Default")
      (node (ref "U$1") (pin "85") (pinfunction "PD1/MTIOC4B/CTX0/AN009_85") (pintype "bidirectional"))
      (node (ref "X11") (pin "12") (pinfunction "S_12") (pintype "passive"))
    )
    (net (code "14") (name "/AN010") (class "Default")
      (node (ref "U$1") (pin "84") (pinfunction "PD2/MTIOC4D/CRX0/AN010_84") (pintype "bidirectional"))
      (node (ref "X11") (pin "13") (pinfunction "S_13") (pintype "passive"))
    )
    (net (code "15") (name "/AN011") (class "Default")
      (node (ref "U$1") (pin "83") (pinfunction "PD3/AN011_83") (pintype "bidirectional"))
      (node (ref "X11") (pin "14") (pinfunction "S_14") (pintype "passive"))
    )
    (net (code "16") (name "/AN012") (class "Default")
      (node (ref "U$1") (pin "82") (pinfunction "PD4/AN012_82") (pintype "bidirectional"))
      (node (ref "X11") (pin "15") (pinfunction "S_15") (pintype "passive"))
    )
    (net (code "17") (name "/AN013") (class "Default")
      (node (ref "U$1") (pin "81") (pinfunction "PD5/AN013_81") (pintype "bidirectional"))
      (node (ref "X11") (pin "16") (pinfunction "S_16") (pintype "passive"))
    )
    (net (code "18") (name "/BCLK") (class "Default")
      (node (ref "U$1") (pin "41") (pinfunction "P53/BCLK_41") (pintype "bidirectional"))
    )
    (net (code "19") (name "/CANH0") (class "Default")
      (node (ref "R10") (pin "2") (pinfunction "2_2") (pintype "passive"))
      (node (ref "U$5") (pin "7") (pinfunction "CANH_7") (pintype "bidirectional"))
      (node (ref "X13") (pin "2") (pinfunction "2_2") (pintype "bidirectional"))
      (node (ref "X15") (pin "2") (pinfunction "2_2") (pintype "bidirectional"))
    )
    (net (code "20") (name "/CANH1") (class "Default")
      (node (ref "R9") (pin "1") (pinfunction "1_1") (pintype "passive"))
      (node (ref "U$4") (pin "7") (pinfunction "CANH_7") (pintype "bidirectional"))
      (node (ref "X16") (pin "2") (pinfunction "2_2") (pintype "bidirectional"))
      (node (ref "X17") (pin "2") (pinfunction "2_2") (pintype "bidirectional"))
    )
    (net (code "21") (name "/CANL0") (class "Default")
      (node (ref "JP3") (pin "1") (pinfunction "1_1") (pintype "passive"))
      (node (ref "U$5") (pin "6") (pinfunction "CANL_6") (pintype "bidirectional"))
      (node (ref "X13") (pin "3") (pinfunction "3_3") (pintype "bidirectional"))
      (node (ref "X15") (pin "3") (pinfunction "3_3") (pintype "bidirectional"))
    )
    (net (code "22") (name "/CANL1") (class "Default")
      (node (ref "JP2") (pin "1") (pinfunction "1_1") (pintype "passive"))
      (node (ref "U$4") (pin "6") (pinfunction "CANL_6") (pintype "bidirectional"))
      (node (ref "X16") (pin "3") (pinfunction "3_3") (pintype "bidirectional"))
      (node (ref "X17") (pin "3") (pinfunction "3_3") (pintype "bidirectional"))
    )
    (net (code "23") (name "/CRX0") (class "Default")
      (node (ref "U$1") (pin "17") (pinfunction "P33/MTIOC0D/RXD6/RXD0/CRX0_17") (pintype "bidirectional"))
      (node (ref "U$5") (pin "4") (pinfunction "RXD_4") (pintype "bidirectional"))
    )
    (net (code "24") (name "/CRX1") (class "Default")
      (node (ref "U$1") (pin "39") (pinfunction "P55/MTIOC4D/CRX1_39") (pintype "bidirectional"))
      (node (ref "U$4") (pin "4") (pinfunction "RXD_4") (pintype "bidirectional"))
    )
    (net (code "25") (name "/CTX0") (class "Default")
      (node (ref "U$1") (pin "18") (pinfunction "P32/MTIOC0C/TXD6/TXD0/CTX0_18") (pintype "bidirectional"))
      (node (ref "U$5") (pin "1") (pinfunction "TXD_1") (pintype "bidirectional"))
    )
    (net (code "26") (name "/CTX1") (class "Default")
      (node (ref "U$1") (pin "40") (pinfunction "P54/MTIOC4B/CTX1_40") (pintype "bidirectional"))
      (node (ref "U$4") (pin "1") (pinfunction "TXD_1") (pintype "bidirectional"))
    )
    (net (code "27") (name "/DA1") (class "Default")
      (node (ref "DAC") (pin "1") (pinfunction "P_1") (pintype "passive"))
      (node (ref "U$1") (pin "100") (pinfunction "P05/DA1_100") (pintype "bidirectional"))
    )
    (net (code "28") (name "/EMLE") (class "Default")
      (node (ref "JP1") (pin "2") (pinfunction "2_2") (pintype "passive"))
      (node (ref "R3") (pin "1") (pinfunction "1_1") (pintype "passive"))
      (node (ref "U$1") (pin "2") (pinfunction "EMLE_2") (pintype "bidirectional"))
      (node (ref "X1") (pin "4") (pinfunction "S_4") (pintype "passive"))
    )
    (net (code "29") (name "/EXTAL") (class "Default")
      (node (ref "C3") (pin "1") (pinfunction "1_1") (pintype "passive"))
      (node (ref "U$1") (pin "13") (pinfunction "P36/EXTAL_13") (pintype "bidirectional"))
      (node (ref "XTAL1") (pin "3") (pinfunction "2_3") (pintype "passive"))
    )
    (net (code "30") (name "/MD") (class "Default")
      (node (ref "R7") (pin "1") (pinfunction "1_1") (pintype "passive"))
      (node (ref "U$1") (pin "7") (pinfunction "MD/FINED_7") (pintype "bidirectional"))
      (node (ref "U$24") (pin "10") (pinfunction "COM1_10") (pintype "bidirectional"))
      (node (ref "X1") (pin "7") (pinfunction "S_7") (pintype "passive"))
    )
    (net (code "31") (name "/MDSW") (class "Default")
      (node (ref "U$24") (pin "9") (pinfunction "NC1_9") (pintype "bidirectional"))
      (node (ref "U$82") (pin "2") (pinfunction "2_2") (pintype "bidirectional"))
      (node (ref "U$82") (pin "5") (pinfunction "5_5") (pintype "bidirectional"))
    )
    (net (code "32") (name "/MISOB") (class "Default")
      (node (ref "U$1") (pin "71") (pinfunction "PE7/AN5_71") (pintype "bidirectional"))
      (node (ref "X10") (pin "6") (pinfunction "6_6") (pintype "bidirectional"))
    )
    (net (code "33") (name "/MOSIB") (class "Default")
      (node (ref "U$1") (pin "72") (pinfunction "PE6/AN4_72") (pintype "bidirectional"))
      (node (ref "X10") (pin "5") (pinfunction "5_5") (pintype "bidirectional"))
    )
    (net (code "34") (name "/MTCLKA") (class "Default")
      (node (ref "U$1") (pin "31") (pinfunction "P15/MTIOC0B/MTCLKB/RXD1/SCK3_31") (pintype "bidirectional"))
      (node (ref "U$10") (pin "2") (pinfunction "2_2") (pintype "passive"))
    )
    (net (code "35") (name "/MTCLKB{slash}USBDPUPE") (class "Default")
      (node (ref "JP8") (pin "5") (pinfunction "5_5") (pintype "passive"))
      (node (ref "U$11") (pin "2") (pinfunction "2_2") (pintype "passive"))
    )
    (net (code "36") (name "/MTCLKC") (class "Default")
      (node (ref "U$1") (pin "48") (pinfunction "PC4/MTIOC3D/MTCLKC/SCK5_48") (pintype "bidirectional"))
      (node (ref "U$8") (pin "2") (pinfunction "2_2") (pintype "passive"))
    )
    (net (code "37") (name "/MTCLKD") (class "Default")
      (node (ref "U$1") (pin "47") (pinfunction "PC5/MTIOC3B/MTCLKD/SCK8_47") (pintype "bidirectional"))
      (node (ref "U$9") (pin "2") (pinfunction "2_2") (pintype "passive"))
    )
    (net (code "38") (name "/MTIOC4A") (class "Default")
      (node (ref "Q4") (pin "1") (pinfunction "G_1") (pintype "bidirectional"))
      (node (ref "R33") (pin "2") (pinfunction "2_2") (pintype "passive"))
      (node (ref "U$1") (pin "76") (pinfunction "PE2/MTIOC4A/RXD12/AN0_76") (pintype "bidirectional"))
    )
    (net (code "39") (name "/P07") (class "Default")
      (node (ref "JP6") (pin "2") (pinfunction "2_2") (pintype "passive"))
      (node (ref "R51") (pin "1") (pinfunction "1_1") (pintype "passive"))
      (node (ref "U$1") (pin "98") (pinfunction "P07_98") (pintype "bidirectional"))
    )
    (net (code "40") (name "/P14") (class "Default")
      (node (ref "JP8") (pin "3") (pinfunction "3_3") (pintype "passive"))
      (node (ref "U$1") (pin "32") (pinfunction "P14/MTIOC3A/MTCLKA/CTX1_32") (pintype "bidirectional"))
    )
    (net (code "41") (name "/P16") (class "Default")
      (node (ref "JP8") (pin "4") (pinfunction "4_4") (pintype "passive"))
      (node (ref "U$1") (pin "30") (pinfunction "P16/MTIOC3C/MTIOC3D/TXD1/RXD3_30") (pintype "bidirectional"))
    )
    (net (code "42") (name "/P22") (class "Default")
      (node (ref "S4") (pin "3") (pinfunction "P_3") (pintype "passive"))
      (node (ref "S4") (pin "4") (pinfunction "P1_4") (pintype "passive"))
      (node (ref "U$1") (pin "26") (pinfunction "P22/MTIOC3B/MTCLKC/SCK0_26") (pintype "bidirectional"))
      (node (ref "U$21") (pin "7") (pinfunction "7_7") (pintype "passive"))
    )
    (net (code "43") (name "/P23") (class "Default")
      (node (ref "S3") (pin "3") (pinfunction "P_3") (pintype "passive"))
      (node (ref "S3") (pin "4") (pinfunction "P1_4") (pintype "passive"))
      (node (ref "U$1") (pin "25") (pinfunction "P23/MTIOC3D/MTCLKD/TXD3_25") (pintype "bidirectional"))
      (node (ref "U$21") (pin "5") (pinfunction "5_5") (pintype "passive"))
    )
    (net (code "44") (name "/P24") (class "Default")
      (node (ref "S2") (pin "3") (pinfunction "P_3") (pintype "passive"))
      (node (ref "S2") (pin "4") (pinfunction "P1_4") (pintype "passive"))
      (node (ref "U$1") (pin "24") (pinfunction "P24/MTIOC4A/MTCLKA/SCK3_24") (pintype "bidirectional"))
      (node (ref "U$21") (pin "3") (pinfunction "3_3") (pintype "passive"))
    )
    (net (code "45") (name "/P25") (class "Default")
      (node (ref "S1") (pin "3") (pinfunction "P_3") (pintype "passive"))
      (node (ref "S1") (pin "4") (pinfunction "P1_4") (pintype "passive"))
      (node (ref "U$1") (pin "23") (pinfunction "P25/MTIOC4C/MTCLKB/RXD3_23") (pintype "bidirectional"))
      (node (ref "U$21") (pin "1") (pinfunction "1_1") (pintype "passive"))
    )
    (net (code "46") (name "/P51") (class "Default")
      (node (ref "U$1") (pin "43") (pinfunction "P51/SCK2_43") (pintype "bidirectional"))
    )
    (net (code "47") (name "/PA0") (class "Default")
      (node (ref "U$1") (pin "70") (pinfunction "PA0/MTIOC4A_70") (pintype "bidirectional"))
      (node (ref "X9") (pin "3") (pinfunction "S_3") (pintype "passive"))
    )
    (net (code "48") (name "/PA1") (class "Default")
      (node (ref "U$1") (pin "69") (pinfunction "PA1/MTIOC0B/MTCLKC/SCK5_69") (pintype "bidirectional"))
      (node (ref "X9") (pin "4") (pinfunction "S_4") (pintype "passive"))
    )
    (net (code "49") (name "/PA2") (class "Default")
      (node (ref "U$1") (pin "68") (pinfunction "PA2/RXD5_68") (pintype "bidirectional"))
      (node (ref "X9") (pin "5") (pinfunction "S_5") (pintype "passive"))
    )
    (net (code "50") (name "/PA3") (class "Default")
      (node (ref "U$1") (pin "67") (pinfunction "PA3/MTIOC0D/MTCLKD/RXD5_67") (pintype "bidirectional"))
      (node (ref "X9") (pin "6") (pinfunction "S_6") (pintype "passive"))
    )
    (net (code "51") (name "/PA4") (class "Default")
      (node (ref "U$1") (pin "66") (pinfunction "PA4/MTCLKA/TXD5_66") (pintype "bidirectional"))
      (node (ref "X9") (pin "7") (pinfunction "S_7") (pintype "passive"))
    )
    (net (code "52") (name "/PA5") (class "Default")
      (node (ref "U$1") (pin "65") (pinfunction "PA5_65") (pintype "bidirectional"))
      (node (ref "X9") (pin "8") (pinfunction "S_8") (pintype "passive"))
    )
    (net (code "53") (name "/PA6") (class "Default")
      (node (ref "U$1") (pin "64") (pinfunction "PA6/MTCLKB_64") (pintype "bidirectional"))
      (node (ref "X9") (pin "9") (pinfunction "S_9") (pintype "passive"))
    )
    (net (code "54") (name "/PA7") (class "Default")
      (node (ref "U$1") (pin "63") (pinfunction "PA7_63") (pintype "bidirectional"))
      (node (ref "X9") (pin "10") (pinfunction "S_10") (pintype "passive"))
    )
    (net (code "55") (name "/PB2") (class "Default")
      (node (ref "U$1") (pin "58") (pinfunction "PB2_58") (pintype "bidirectional"))
      (node (ref "U$12") (pin "5") (pinfunction "RESET_5") (pintype "bidirectional"))
    )
    (net (code "56") (name "/PB3") (class "Default")
      (node (ref "Q3") (pin "1") (pinfunction "G_1") (pintype "bidirectional"))
      (node (ref "U$1") (pin "57") (pinfunction "PB3/MTIOC0A/MTIOC4A/SCK6_57") (pintype "bidirectional"))
      (node (ref "U$17") (pin "2") (pinfunction "2_2") (pintype "passive"))
    )
    (net (code "57") (name "/PB4") (class "Default")
      (node (ref "U$1") (pin "56") (pinfunction "PB4_56") (pintype "bidirectional"))
      (node (ref "U$17") (pin "4") (pinfunction "4_4") (pintype "passive"))
      (node (ref "U$58") (pin "3") (pinfunction "SW_3") (pintype "bidirectional"))
    )
    (net (code "58") (name "/PB5") (class "Default")
      (node (ref "C15") (pin "1") (pinfunction "1_1") (pintype "passive"))
      (node (ref "R20") (pin "2") (pinfunction "2_2") (pintype "passive"))
      (node (ref "U$1") (pin "55") (pinfunction "PB5/MTIOC2A/MTIOC1B/SCK9_55") (pintype "bidirectional"))
      (node (ref "U$58") (pin "8") (pinfunction "A_8") (pintype "bidirectional"))
    )
    (net (code "59") (name "/PB6") (class "Default")
      (node (ref "U$1") (pin "54") (pinfunction "PB6/MTIOC3D/RXD9_54") (pintype "bidirectional"))
    )
    (net (code "60") (name "/PB7") (class "Default")
      (node (ref "C14") (pin "1") (pinfunction "1_1") (pintype "passive"))
      (node (ref "R19") (pin "2") (pinfunction "2_2") (pintype "passive"))
      (node (ref "U$1") (pin "53") (pinfunction "PB7/MTIOC3B/TXD9_53") (pintype "bidirectional"))
      (node (ref "U$58") (pin "6") (pinfunction "B_6") (pintype "bidirectional"))
    )
    (net (code "61") (name "/PC0") (class "Default")
      (node (ref "Q2") (pin "1") (pinfunction "G_1") (pintype "bidirectional"))
      (node (ref "U$1") (pin "52") (pinfunction "PC0/MTIOC3C_52") (pintype "bidirectional"))
      (node (ref "U$17") (pin "6") (pinfunction "6_6") (pintype "passive"))
    )
    (net (code "62") (name "/PC1") (class "Default")
      (node (ref "Q1") (pin "1") (pinfunction "G_1") (pintype "bidirectional"))
      (node (ref "U$1") (pin "51") (pinfunction "PC1/MTIOC3A/TCLKA/RXD5_51") (pintype "bidirectional"))
      (node (ref "U$17") (pin "8") (pinfunction "8_8") (pintype "passive"))
    )
    (net (code "63") (name "/PC6") (class "Default")
      (node (ref "U$1") (pin "46") (pinfunction "PC6/MTIOC3C/MTCLKA/RXD8_46") (pintype "bidirectional"))
    )
    (net (code "64") (name "/PC7") (class "Default")
      (node (ref "JP9") (pin "2") (pinfunction "2_2") (pintype "passive"))
      (node (ref "R8") (pin "2") (pinfunction "2_2") (pintype "passive"))
      (node (ref "U$1") (pin "45") (pinfunction "PC7/MTIOC3A/MTCLKB/TXD8_45") (pintype "bidirectional"))
      (node (ref "X1") (pin "10") (pinfunction "S_10") (pintype "passive"))
    )
    (net (code "65") (name "/PD6") (class "Default")
      (node (ref "LED4") (pin "A") (pinfunction "A_A") (pintype "passive"))
      (node (ref "U$1") (pin "80") (pinfunction "PD6/AN6_80") (pintype "bidirectional"))
    )
    (net (code "66") (name "/PD7") (class "Default")
      (node (ref "LED3") (pin "A") (pinfunction "A_A") (pintype "passive"))
      (node (ref "U$1") (pin "79") (pinfunction "PD7/AN7_79") (pintype "bidirectional"))
    )
    (net (code "67") (name "/PE0") (class "Default")
      (node (ref "LED2") (pin "A") (pinfunction "A_A") (pintype "passive"))
      (node (ref "U$1") (pin "78") (pinfunction "PE0/SCK12/ANEX0_78") (pintype "bidirectional"))
    )
    (net (code "68") (name "/PE1") (class "Default")
      (node (ref "LED1") (pin "A") (pinfunction "A_A") (pintype "passive"))
      (node (ref "U$1") (pin "77") (pinfunction "PE1/MTIOC4C/TXD12/ANEX1_77") (pintype "bidirectional"))
    )
    (net (code "69") (name "/PE3") (class "Default")
      (node (ref "LED9") (pin "A") (pinfunction "A_A") (pintype "passive"))
      (node (ref "U$1") (pin "75") (pinfunction "PE3/MTIOC4B/AN1_75") (pintype "bidirectional"))
    )
    (net (code "70") (name "/RES#") (class "Default")
      (node (ref "R35") (pin "2") (pinfunction "2_2") (pintype "passive"))
      (node (ref "U$1") (pin "10") (pinfunction "RES#_10") (pintype "bidirectional"))
      (node (ref "U$24") (pin "6") (pinfunction "COM2_6") (pintype "bidirectional"))
      (node (ref "X1") (pin "13") (pinfunction "S_13") (pintype "passive"))
    )
    (net (code "71") (name "/RESETSW") (class "Default")
      (node (ref "S5") (pin "1") (pinfunction "S_1") (pintype "passive"))
      (node (ref "S5") (pin "2") (pinfunction "S1_2") (pintype "passive"))
      (node (ref "U$24") (pin "7") (pinfunction "NC2_7") (pintype "bidirectional"))
    )
    (net (code "72") (name "/RSPCKB") (class "Default")
      (node (ref "U$1") (pin "73") (pinfunction "PE5/MTIOC4C/MTIOC2B/AN3_73") (pintype "bidirectional"))
      (node (ref "X10") (pin "4") (pinfunction "4_4") (pintype "bidirectional"))
    )
    (net (code "73") (name "/RXD0") (class "Default")
      (node (ref "JP4") (pin "1") (pinfunction "1_1") (pintype "passive"))
      (node (ref "U$1") (pin "27") (pinfunction "P21/MTIOC1B/RXD0_27") (pintype "bidirectional"))
    )
    (net (code "74") (name "/RXD1") (class "Default")
      (node (ref "U$1") (pin "20") (pinfunction "P30/TDI/MTIOC4B/RXD1_20") (pintype "bidirectional"))
      (node (ref "U$23") (pin "3") (pinfunction "3_3") (pintype "passive"))
      (node (ref "U$25") (pin "6") (pinfunction "COM2_6") (pintype "bidirectional"))
      (node (ref "X1") (pin "11") (pinfunction "S_11") (pintype "passive"))
    )
    (net (code "75") (name "/RXD2") (class "Default")
      (node (ref "U$1") (pin "42") (pinfunction "P52/RXD2_42") (pintype "bidirectional"))
      (node (ref "X5") (pin "3") (pinfunction "3_3") (pintype "bidirectional"))
    )
    (net (code "76") (name "/RXD3{slash}FT231TXD") (class "Default")
      (node (ref "FT231XS") (pin "20") (pinfunction "TXD_20") (pintype "bidirectional"))
      (node (ref "JP8") (pin "6") (pinfunction "6_6") (pintype "passive"))
      (node (ref "U$25") (pin "7") (pinfunction "NC2_7") (pintype "bidirectional"))
    )
    (net (code "77") (name "/RXD5") (class "Default")
      (node (ref "U$1") (pin "50") (pinfunction "PC2/MTIOC4B/TCLKA/RXD5_50") (pintype "bidirectional"))
      (node (ref "X6") (pin "3") (pinfunction "3_3") (pintype "bidirectional"))
    )
    (net (code "78") (name "/RXD6") (class "Default")
      (node (ref "U$1") (pin "61") (pinfunction "PB0/RXD6_61") (pintype "bidirectional"))
      (node (ref "U$12") (pin "14") (pinfunction "UART_TX_14") (pintype "bidirectional"))
    )
    (net (code "79") (name "/SBDBTMD") (class "Default")
      (node (ref "IC6") (pin "43") (pinfunction "RB7_43") (pintype "bidirectional"))
      (node (ref "U$24") (pin "2") (pinfunction "NO1_2") (pintype "bidirectional"))
    )
    (net (code "80") (name "/SBDBTRESET") (class "Default")
      (node (ref "IC6") (pin "44") (pinfunction "RB8_44") (pintype "bidirectional"))
      (node (ref "U$24") (pin "4") (pinfunction "NO2_4") (pintype "bidirectional"))
    )
    (net (code "81") (name "/SBDBTRX") (class "Default")
      (node (ref "IC6") (pin "3") (pinfunction "RC7_3") (pintype "bidirectional"))
      (node (ref "U$25") (pin "2") (pinfunction "NO1_2") (pintype "bidirectional"))
    )
    (net (code "82") (name "/SBDBTSW0") (class "Default")
      (node (ref "IC6") (pin "41") (pinfunction "RB5_41") (pintype "bidirectional"))
      (node (ref "R5") (pin "2") (pinfunction "2_2") (pintype "passive"))
      (node (ref "U$25") (pin "1") (pinfunction "IN1_1") (pintype "bidirectional"))
      (node (ref "U$25") (pin "5") (pinfunction "IN2_5") (pintype "bidirectional"))
    )
    (net (code "83") (name "/SBDBTSW1") (class "Default")
      (node (ref "IC6") (pin "1") (pinfunction "RB9_1") (pintype "bidirectional"))
      (node (ref "R2") (pin "2") (pinfunction "2_2") (pintype "passive"))
      (node (ref "U$24") (pin "1") (pinfunction "IN1_1") (pintype "bidirectional"))
      (node (ref "U$24") (pin "5") (pinfunction "IN2_5") (pintype "bidirectional"))
    )
    (net (code "84") (name "/SBDBTTX") (class "Default")
      (node (ref "IC6") (pin "2") (pinfunction "RC6_2") (pintype "bidirectional"))
      (node (ref "U$25") (pin "4") (pinfunction "NO2_4") (pintype "bidirectional"))
    )
    (net (code "85") (name "/SCL0") (class "Default")
      (node (ref "SJ1") (pin "1") (pinfunction "1_1") (pintype "passive"))
      (node (ref "U$1") (pin "34") (pinfunction "P12/RXD2_34") (pintype "bidirectional"))
      (node (ref "X4") (pin "3") (pinfunction "3_3") (pintype "bidirectional"))
    )
    (net (code "86") (name "/SDA0") (class "Default")
      (node (ref "SJ2") (pin "1") (pinfunction "1_1") (pintype "passive"))
      (node (ref "U$1") (pin "33") (pinfunction "P13/MTIOC0B/TXD2_33") (pintype "bidirectional"))
      (node (ref "X4") (pin "4") (pinfunction "4_4") (pintype "bidirectional"))
    )
    (net (code "87") (name "/SSLB0") (class "Default")
      (node (ref "U$1") (pin "74") (pinfunction "PE4/MTIOC4D/MTIOC1A/AN2_74") (pintype "bidirectional"))
      (node (ref "X10") (pin "3") (pinfunction "3_3") (pintype "bidirectional"))
    )
    (net (code "88") (name "/TCK") (class "Default")
      (node (ref "U$1") (pin "21") (pinfunction "P27/TCK/MTIOC2B/SCK1_21") (pintype "bidirectional"))
      (node (ref "U$23") (pin "5") (pinfunction "5_5") (pintype "passive"))
      (node (ref "X1") (pin "1") (pinfunction "S_1") (pintype "passive"))
    )
    (net (code "89") (name "/TMS") (class "Default")
      (node (ref "U$1") (pin "19") (pinfunction "P31/TMS/MTIOC4D_19") (pintype "bidirectional"))
      (node (ref "U$23") (pin "1") (pinfunction "1_1") (pintype "passive"))
      (node (ref "X1") (pin "9") (pinfunction "S_9") (pintype "passive"))
    )
    (net (code "90") (name "/TRST#") (class "Default")
      (node (ref "R4") (pin "2") (pinfunction "2_2") (pintype "passive"))
      (node (ref "U$1") (pin "16") (pinfunction "P34/MTIOC0A/SCK6/SCK0/USB0_DPRPD_16") (pintype "bidirectional"))
      (node (ref "X1") (pin "3") (pinfunction "S_3") (pintype "passive"))
    )
    (net (code "91") (name "/TXD0") (class "Default")
      (node (ref "JP4") (pin "2") (pinfunction "2_2") (pintype "passive"))
      (node (ref "U$1") (pin "28") (pinfunction "P20/MTIOC1A/TXD0_28") (pintype "bidirectional"))
    )
    (net (code "92") (name "/TXD1") (class "Default")
      (node (ref "U$1") (pin "22") (pinfunction "P26/TDO/MTIOC2A/TXD1_22") (pintype "bidirectional"))
      (node (ref "U$23") (pin "7") (pinfunction "7_7") (pintype "passive"))
      (node (ref "U$25") (pin "10") (pinfunction "COM1_10") (pintype "bidirectional"))
      (node (ref "X1") (pin "5") (pinfunction "S_5") (pintype "passive"))
    )
    (net (code "93") (name "/TXD2") (class "Default")
      (node (ref "U$1") (pin "44") (pinfunction "P50/TXD2_44") (pintype "bidirectional"))
      (node (ref "X5") (pin "4") (pinfunction "4_4") (pintype "bidirectional"))
    )
    (net (code "94") (name "/TXD3{slash}FT231RXD") (class "Default")
      (node (ref "FT231XS") (pin "4") (pinfunction "RXD_4") (pintype "bidirectional"))
      (node (ref "U$1") (pin "29") (pinfunction "P17/MTIOC3A/MTIOC3B/SCK1/TXD3_29") (pintype "bidirectional"))
      (node (ref "U$25") (pin "9") (pinfunction "NC1_9") (pintype "bidirectional"))
    )
    (net (code "95") (name "/TXD5") (class "Default")
      (node (ref "U$1") (pin "49") (pinfunction "PC3/MTIOC4D/TCLKB/TXD5_49") (pintype "bidirectional"))
      (node (ref "X6") (pin "4") (pinfunction "4_4") (pintype "bidirectional"))
    )
    (net (code "96") (name "/TXD6") (class "Default")
      (node (ref "U$1") (pin "59") (pinfunction "PB1/MTIOC0C/MTIOC4C/TXD6_59") (pintype "bidirectional"))
      (node (ref "U$12") (pin "13") (pinfunction "UART_RX_13") (pintype "bidirectional"))
    )
    (net (code "97") (name "/USB0VBUS") (class "Default")
      (node (ref "C27") (pin "2") (pinfunction "2_2") (pintype "passive"))
      (node (ref "JP8") (pin "2") (pinfunction "2_2") (pintype "passive"))
      (node (ref "R46") (pin "2") (pinfunction "2_2") (pintype "passive"))
      (node (ref "R47") (pin "1") (pinfunction "1_1") (pintype "passive"))
    )
    (net (code "98") (name "/USB0_DM") (class "Default")
      (node (ref "R45") (pin "2") (pinfunction "2_2") (pintype "passive"))
      (node (ref "U$1") (pin "36") (pinfunction "USB0_DM_36") (pintype "bidirectional"))
    )
    (net (code "99") (name "/USB0_DP") (class "Default")
      (node (ref "R44") (pin "2") (pinfunction "2_2") (pintype "passive"))
      (node (ref "R48") (pin "2") (pinfunction "2_2") (pintype "passive"))
      (node (ref "U$1") (pin "37") (pinfunction "USB0_DP_37") (pintype "bidirectional"))
    )
    (net (code "100") (name "/USBDPUPE") (class "Default")
      (node (ref "JP8") (pin "1") (pinfunction "1_1") (pintype "passive"))
      (node (ref "R48") (pin "1") (pinfunction "1_1") (pintype "passive"))
    )
    (net (code "101") (name "/XCIN") (class "Default")
      (node (ref "C4") (pin "2") (pinfunction "2_2") (pintype "passive"))
      (node (ref "U$1") (pin "8") (pinfunction "XCIN_8") (pintype "bidirectional"))
      (node (ref "U$3") (pin "1") (pinfunction "1_1") (pintype "bidirectional"))
    )
    (net (code "102") (name "/XCOUT") (class "Default")
      (node (ref "C5") (pin "2") (pinfunction "2_2") (pintype "passive"))
      (node (ref "U$1") (pin "9") (pinfunction "XCOUT_9") (pintype "bidirectional"))
      (node (ref "U$3") (pin "2") (pinfunction "2_2") (pintype "bidirectional"))
    )
    (net (code "103") (name "/XTAL") (class "Default")
      (node (ref "C2") (pin "1") (pinfunction "1_1") (pintype "passive"))
      (node (ref "U$1") (pin "11") (pinfunction "P37/XTAL_11") (pintype "bidirectional"))
      (node (ref "XTAL1") (pin "1") (pinfunction "1_1") (pintype "passive"))
    )
    (net (code "104") (name "GND") (class "Default")
      (node (ref "C1") (pin "2") (pinfunction "2_2") (pintype "passive"))
      (node (ref "C10") (pin "1") (pinfunction "1_1") (pintype "passive"))
      (node (ref "C11") (pin "1") (pinfunction "1_1") (pintype "passive"))
      (node (ref "C12") (pin "1") (pinfunction "1_1") (pintype "passive"))
      (node (ref "C13") (pin "1") (pinfunction "1_1") (pintype "passive"))
      (node (ref "C14") (pin "2") (pinfunction "2_2") (pintype "passive"))
      (node (ref "C15") (pin "2") (pinfunction "2_2") (pintype "passive"))
      (node (ref "C16") (pin "2") (pinfunction "2_2") (pintype "passive"))
      (node (ref "C17") (pin "2") (pinfunction "2_2") (pintype "passive"))
      (node (ref "C18") (pin "2") (pinfunction "2_2") (pintype "passive"))
      (node (ref "C19") (pin "2") (pinfunction "2_2") (pintype "passive"))
      (node (ref "C2") (pin "2") (pinfunction "2_2") (pintype "passive"))
      (node (ref "C20") (pin "2") (pinfunction "2_2") (pintype "passive"))
      (node (ref "C21") (pin "1") (pinfunction "1_1") (pintype "passive"))
      (node (ref "C22") (pin "1") (pinfunction "1_1") (pintype "passive"))
      (node (ref "C23") (pin "1") (pinfunction "1_1") (pintype "passive"))
      (node (ref "C24") (pin "2") (pinfunction "2_2") (pintype "passive"))
      (node (ref "C25") (pin "2") (pinfunction "2_2") (pintype "passive"))
      (node (ref "C26") (pin "2") (pinfunction "2_2") (pintype "passive"))
      (node (ref "C27") (pin "1") (pinfunction "1_1") (pintype "passive"))
      (node (ref "C28") (pin "2") (pinfunction "2_2") (pintype "passive"))
      (node (ref "C29") (pin "2") (pinfunction "2_2") (pintype "passive"))
      (node (ref "C3") (pin "2") (pinfunction "2_2") (pintype "passive"))
      (node (ref "C30") (pin "1") (pinfunction "1_1") (pintype "passive"))
      (node (ref "C31") (pin "2") (pinfunction "2_2") (pintype "passive"))
      (node (ref "C32") (pin "2") (pinfunction "2_2") (pintype "passive"))
      (node (ref "C33") (pin "2") (pinfunction "2_2") (pintype "passive"))
      (node (ref "C34") (pin "2") (pinfunction "2_2") (pintype "passive"))
      (node (ref "C4") (pin "1") (pinfunction "1_1") (pintype "passive"))
      (node (ref "C5") (pin "1") (pinfunction "1_1") (pintype "passive"))
      (node (ref "C6") (pin "2") (pinfunction "2_2") (pintype "passive"))
      (node (ref "C7") (pin "2") (pinfunction "2_2") (pintype "passive"))
      (node (ref "C8") (pin "2") (pinfunction "2_2") (pintype "passive"))
      (node (ref "C9") (pin "2") (pinfunction "2_2") (pintype "passive"))
      (node (ref "FT231XS") (pin "16") (pinfunction "GND_16") (pintype "power_in"))
      (node (ref "FT231XS") (pin "6") (pinfunction "GND_6") (pintype "power_in"))
      (node (ref "GNDPAD0") (pin "1") (pinfunction "P_1") (pintype "passive"))
      (node (ref "GNDPAD1") (pin "1") (pinfunction "P_1") (pintype "passive"))
      (node (ref "IC1") (pin "1") (pinfunction "GND_1") (pintype "power_in"))
      (node (ref "IC6") (pin "16") (pinfunction "AVSS_16") (pintype "power_in"))
      (node (ref "IC6") (pin "29") (pinfunction "VSS_29") (pintype "power_in"))
      (node (ref "IC6") (pin "39") (pinfunction "VSS_39") (pintype "power_in"))
      (node (ref "IC6") (pin "6") (pinfunction "DISVREG_6") (pintype "passive"))
      (node (ref "JP1") (pin "1") (pinfunction "1_1") (pintype "passive"))
      (node (ref "JP4") (pin "6") (pinfunction "6_6") (pintype "passive"))
      (node (ref "JP6") (pin "1") (pinfunction "1_1") (pintype "passive"))
      (node (ref "JP7") (pin "3") (pinfunction "3_3") (pintype "passive"))
      (node (ref "Q1") (pin "2") (pinfunction "S_2") (pintype "bidirectional"))
      (node (ref "Q2") (pin "2") (pinfunction "S_2") (pintype "bidirectional"))
      (node (ref "Q3") (pin "2") (pinfunction "S_2") (pintype "bidirectional"))
      (node (ref "Q4") (pin "2") (pinfunction "S_2") (pintype "bidirectional"))
      (node (ref "R11") (pin "1") (pinfunction "1_1") (pintype "passive"))
      (node (ref "R2") (pin "1") (pinfunction "1_1") (pintype "passive"))
      (node (ref "R25") (pin "1") (pinfunction "1_1") (pintype "passive"))
      (node (ref "R26") (pin "1") (pinfunction "1_1") (pintype "passive"))
      (node (ref "R27") (pin "1") (pinfunction "1_1") (pintype "passive"))
      (node (ref "R28") (pin "1") (pinfunction "1_1") (pintype "passive"))
      (node (ref "R33") (pin "1") (pinfunction "1_1") (pintype "passive"))
      (node (ref "R34") (pin "1") (pinfunction "1_1") (pintype "passive"))
      (node (ref "R4") (pin "1") (pinfunction "1_1") (pintype "passive"))
      (node (ref "R47") (pin "2") (pinfunction "2_2") (pintype "passive"))
      (node (ref "R49") (pin "1") (pinfunction "1_1") (pintype "passive"))
      (node (ref "R5") (pin "1") (pinfunction "1_1") (pintype "passive"))
      (node (ref "R50") (pin "1") (pinfunction "1_1") (pintype "passive"))
      (node (ref "R8") (pin "1") (pinfunction "1_1") (pintype "passive"))
      (node (ref "S1") (pin "1") (pinfunction "S_1") (pintype "passive"))
      (node (ref "S1") (pin "2") (pinfunction "S1_2") (pintype "passive"))
      (node (ref "S2") (pin "1") (pinfunction "S_1") (pintype "passive"))
      (node (ref "S2") (pin "2") (pinfunction "S1_2") (pintype "passive"))
      (node (ref "S3") (pin "1") (pinfunction "S_1") (pintype "passive"))
      (node (ref "S3") (pin "2") (pinfunction "S1_2") (pintype "passive"))
      (node (ref "S4") (pin "1") (pinfunction "S_1") (pintype "passive"))
      (node (ref "S4") (pin "2") (pinfunction "S1_2") (pintype "passive"))
      (node (ref "S5") (pin "3") (pinfunction "P_3") (pintype "passive"))
      (node (ref "S5") (pin "4") (pinfunction "P1_4") (pintype "passive"))
      (node (ref "U$1") (pin "12") (pinfunction "VSS_12") (pintype "bidirectional"))
      (node (ref "U$1") (pin "3") (pinfunction "VREFL_3") (pintype "bidirectional"))
      (node (ref "U$1") (pin "38") (pinfunction "VSS_USB_38") (pintype "bidirectional"))
      (node (ref "U$1") (pin "62") (pinfunction "VSS_62") (pintype "bidirectional"))
      (node (ref "U$1") (pin "94") (pinfunction "VREFL0_94") (pintype "bidirectional"))
      (node (ref "U$1") (pin "99") (pinfunction "AVSS0_99") (pintype "bidirectional"))
      (node (ref "U$12") (pin "1") (pinfunction "GND_1") (pintype "power_in"))
      (node (ref "U$12") (pin "12") (pinfunction "GND_12") (pintype "power_in"))
      (node (ref "U$12") (pin "28") (pinfunction "GND_28") (pintype "power_in"))
      (node (ref "U$12") (pin "29") (pinfunction "GND_29") (pintype "power_in"))
      (node (ref "U$13") (pin "2") (pinfunction "GND_2") (pintype "power_in"))
      (node (ref "U$14") (pin "2") (pinfunction "GND_2") (pintype "power_in"))
      (node (ref "U$16") (pin "2") (pinfunction "2_2") (pintype "bidirectional"))
      (node (ref "U$16") (pin "5") (pinfunction "5_5") (pintype "bidirectional"))
      (node (ref "U$17") (pin "1") (pinfunction "1_1") (pintype "passive"))
      (node (ref "U$17") (pin "3") (pinfunction "3_3") (pintype "passive"))
      (node (ref "U$17") (pin "5") (pinfunction "5_5") (pintype "passive"))
      (node (ref "U$17") (pin "7") (pinfunction "7_7") (pintype "passive"))
      (node (ref "U$22") (pin "5") (pinfunction "GND_5") (pintype "power_in"))
      (node (ref "U$22") (pin "SHLD1") (pinfunction "SHLD_SHLD1") (pintype "bidirectional"))
      (node (ref "U$22") (pin "SHLD2") (pinfunction "SHLD_SHLD2") (pintype "bidirectional"))
      (node (ref "U$22") (pin "SHLD3") (pinfunction "SHLD_SHLD3") (pintype "bidirectional"))
      (node (ref "U$22") (pin "SHLD4") (pinfunction "SHLD_SHLD4") (pintype "bidirectional"))
      (node (ref "U$24") (pin "3") (pinfunction "GND_3") (pintype "bidirectional"))
      (node (ref "U$25") (pin "3") (pinfunction "GND_3") (pintype "bidirectional"))
      (node (ref "U$4") (pin "2") (pinfunction "VSS_2") (pintype "power_in"))
      (node (ref "U$4") (pin "8") (pinfunction "STBY_8") (pintype "bidirectional"))
      (node (ref "U$5") (pin "2") (pinfunction "VSS_2") (pintype "power_in"))
      (node (ref "U$5") (pin "8") (pinfunction "STBY_8") (pintype "bidirectional"))
      (node (ref "U$58") (pin "7") (pinfunction "C_7") (pintype "bidirectional"))
      (node (ref "U$82") (pin "1") (pinfunction "1_1") (pintype "bidirectional"))
      (node (ref "U$82") (pin "4") (pinfunction "4_4") (pintype "bidirectional"))
      (node (ref "X1") (pin "12") (pinfunction "S_12") (pintype "passive"))
      (node (ref "X1") (pin "14") (pinfunction "S_14") (pintype "passive"))
      (node (ref "X1") (pin "2") (pinfunction "S_2") (pintype "passive"))
      (node (ref "X10") (pin "2") (pinfunction "2_2") (pintype "bidirectional"))
      (node (ref "X11") (pin "2") (pinfunction "S_2") (pintype "passive"))
      (node (ref "X12") (pin "2") (pinfunction "2_2") (pintype "bidirectional"))
      (node (ref "X13") (pin "1") (pinfunction "1_1") (pintype "bidirectional"))
      (node (ref "X14") (pin "4") (pinfunction "4_4") (pintype "passive"))
      (node (ref "X15") (pin "1") (pinfunction "1_1") (pintype "bidirectional"))
      (node (ref "X16") (pin "1") (pinfunction "1_1") (pintype "bidirectional"))
      (node (ref "X17") (pin "1") (pinfunction "1_1") (pintype "bidirectional"))
      (node (ref "X2") (pin "2") (pinfunction "2_2") (pintype "bidirectional"))
      (node (ref "X3") (pin "4") (pinfunction "4_4") (pintype "passive"))
      (node (ref "X3") (pin "S1") (pinfunction "S1_S1") (pintype "passive"))
      (node (ref "X3") (pin "S2") (pinfunction "S2_S2") (pintype "passive"))
      (node (ref "X4") (pin "2") (pinfunction "2_2") (pintype "bidirectional"))
      (node (ref "X5") (pin "2") (pinfunction "2_2") (pintype "bidirectional"))
      (node (ref "X6") (pin "2") (pinfunction "2_2") (pintype "bidirectional"))
      (node (ref "X7") (pin "2") (pinfunction "2_2") (pintype "bidirectional"))
      (node (ref "X8") (pin "2") (pinfunction "2_2") (pintype "bidirectional"))
      (node (ref "X9") (pin "2") (pinfunction "S_2") (pintype "passive"))
      (node (ref "XTAL1") (pin "2") (pinfunction "GND1_2") (pintype "passive"))
      (node (ref "XTAL1") (pin "4") (pinfunction "GND2_4") (pintype "passive"))
    )
    (net (code "105") (name "Net-(C10-Pad2)") (class "Default")
      (node (ref "C10") (pin "2") (pinfunction "2_2") (pintype "passive"))
      (node (ref "D1") (pin "A") (pinfunction "A_A") (pintype "passive"))
      (node (ref "R15") (pin "1") (pinfunction "1_1") (pintype "passive"))
      (node (ref "U$8") (pin "1") (pinfunction "1_1") (pintype "passive"))
    )
    (net (code "106") (name "Net-(C11-Pad2)") (class "Default")
      (node (ref "C11") (pin "2") (pinfunction "2_2") (pintype "passive"))
      (node (ref "D2") (pin "A") (pinfunction "A_A") (pintype "passive"))
      (node (ref "R16") (pin "1") (pinfunction "1_1") (pintype "passive"))
      (node (ref "U$9") (pin "1") (pinfunction "1_1") (pintype "passive"))
    )
    (net (code "107") (name "Net-(C12-Pad2)") (class "Default")
      (node (ref "C12") (pin "2") (pinfunction "2_2") (pintype "passive"))
      (node (ref "D3") (pin "A") (pinfunction "A_A") (pintype "passive"))
      (node (ref "R17") (pin "1") (pinfunction "1_1") (pintype "passive"))
      (node (ref "U$10") (pin "1") (pinfunction "1_1") (pintype "passive"))
    )
    (net (code "108") (name "Net-(C13-Pad2)") (class "Default")
      (node (ref "C13") (pin "2") (pinfunction "2_2") (pintype "passive"))
      (node (ref "D4") (pin "A") (pinfunction "A_A") (pintype "passive"))
      (node (ref "R18") (pin "1") (pinfunction "1_1") (pintype "passive"))
      (node (ref "U$11") (pin "1") (pinfunction "1_1") (pintype "passive"))
    )
    (net (code "109") (name "Net-(C22-Pad2)") (class "Default")
      (node (ref "C22") (pin "2") (pinfunction "2_2") (pintype "passive"))
      (node (ref "R41") (pin "1") (pinfunction "1_1") (pintype "passive"))
      (node (ref "X14") (pin "3") (pinfunction "3_3") (pintype "passive"))
    )
    (net (code "110") (name "Net-(C23-Pad2)") (class "Default")
      (node (ref "C23") (pin "2") (pinfunction "2_2") (pintype "passive"))
      (node (ref "R40") (pin "1") (pinfunction "1_1") (pintype "passive"))
      (node (ref "X14") (pin "2") (pinfunction "2_2") (pintype "passive"))
    )
    (net (code "111") (name "Net-(D1-C)") (class "Default")
      (node (ref "D1") (pin "K") (pinfunction "C_K") (pintype "passive"))
      (node (ref "X8") (pin "3") (pinfunction "3_3") (pintype "bidirectional"))
    )
    (net (code "112") (name "Net-(D2-C)") (class "Default")
      (node (ref "D2") (pin "K") (pinfunction "C_K") (pintype "passive"))
      (node (ref "X8") (pin "4") (pinfunction "4_4") (pintype "bidirectional"))
    )
    (net (code "113") (name "Net-(D3-C)") (class "Default")
      (node (ref "D3") (pin "K") (pinfunction "C_K") (pintype "passive"))
      (node (ref "X7") (pin "3") (pinfunction "3_3") (pintype "bidirectional"))
    )
    (net (code "114") (name "Net-(D4-C)") (class "Default")
      (node (ref "D4") (pin "K") (pinfunction "C_K") (pintype "passive"))
      (node (ref "X7") (pin "4") (pinfunction "4_4") (pintype "bidirectional"))
    )
    (net (code "115") (name "Net-(D7-PadC)") (class "Default")
      (node (ref "D7") (pin "C") (pinfunction "C_C") (pintype "passive"))
      (node (ref "U$18") (pin "1") (pinfunction "1_1") (pintype "passive"))
      (node (ref "X14") (pin "1") (pinfunction "1_1") (pintype "passive"))
    )
    (net (code "116") (name "Net-(FT231XS-3V3OUT)") (class "Default")
      (node (ref "C21") (pin "2") (pinfunction "2_2") (pintype "passive"))
      (node (ref "FT231XS") (pin "13") (pinfunction "3V3OUT_13") (pintype "power_in"))
      (node (ref "FT231XS") (pin "14") (pinfunction "RESET#_14") (pintype "bidirectional"))
      (node (ref "FT231XS") (pin "3") (pinfunction "VCCIO_3") (pintype "power_in"))
    )
    (net (code "117") (name "Net-(FT231XS-USBDM)") (class "Default")
      (node (ref "FT231XS") (pin "12") (pinfunction "USBDM_12") (pintype "bidirectional"))
      (node (ref "R40") (pin "2") (pinfunction "2_2") (pintype "passive"))
    )
    (net (code "118") (name "Net-(FT231XS-USBDP)") (class "Default")
      (node (ref "FT231XS") (pin "11") (pinfunction "USBDP_11") (pintype "bidirectional"))
      (node (ref "R41") (pin "2") (pinfunction "2_2") (pintype "passive"))
    )
    (net (code "119") (name "Net-(FT231XS-VCC)") (class "Default")
      (node (ref "C24") (pin "1") (pinfunction "1_1") (pintype "passive"))
      (node (ref "C25") (pin "1") (pinfunction "1_1") (pintype "passive"))
      (node (ref "FT231XS") (pin "15") (pinfunction "VCC_15") (pintype "power_in"))
      (node (ref "U$18") (pin "2") (pinfunction "2_2") (pintype "passive"))
    )
    (net (code "120") (name "Net-(IC1-~{RES})") (class "Default")
      (node (ref "IC1") (pin "2") (pinfunction "~{RES}_2") (pintype "output"))
      (node (ref "R35") (pin "1") (pinfunction "1_1") (pintype "passive"))
    )
    (net (code "121") (name "Net-(IC6-RB0)") (class "Default")
      (node (ref "IC6") (pin "21") (pinfunction "RB0_21") (pintype "bidirectional"))
      (node (ref "JP7") (pin "4") (pinfunction "4_4") (pintype "passive"))
    )
    (net (code "122") (name "Net-(IC6-RB1)") (class "Default")
      (node (ref "IC6") (pin "22") (pinfunction "RB1_22") (pintype "bidirectional"))
      (node (ref "JP7") (pin "5") (pinfunction "5_5") (pintype "passive"))
    )
    (net (code "123") (name "Net-(IC6-RB10)") (class "Default")
      (node (ref "IC6") (pin "8") (pinfunction "RB10_8") (pintype "bidirectional"))
      (node (ref "X3") (pin "3") (pinfunction "3_3") (pintype "passive"))
    )
    (net (code "124") (name "Net-(IC6-RB11)") (class "Default")
      (node (ref "IC6") (pin "9") (pinfunction "RB11_9") (pintype "bidirectional"))
      (node (ref "X3") (pin "2") (pinfunction "2_2") (pintype "passive"))
    )
    (net (code "125") (name "Net-(IC6-RB14)") (class "Default")
      (node (ref "IC6") (pin "14") (pinfunction "RB14_14") (pintype "bidirectional"))
      (node (ref "LED12") (pin "A") (pinfunction "A_A") (pintype "passive"))
    )
    (net (code "126") (name "Net-(IC6-RB15)") (class "Default")
      (node (ref "IC6") (pin "15") (pinfunction "RB15_15") (pintype "bidirectional"))
      (node (ref "LED13") (pin "A") (pinfunction "A_A") (pintype "passive"))
    )
    (net (code "127") (name "Net-(IC6-RC8)") (class "Default")
      (node (ref "IC6") (pin "4") (pinfunction "RC8_4") (pintype "bidirectional"))
      (node (ref "IC6") (pin "5") (pinfunction "RC9_5") (pintype "bidirectional"))
    )
    (net (code "128") (name "Net-(IC6-VDDCORE)") (class "Default")
      (node (ref "C32") (pin "1") (pinfunction "1_1") (pintype "passive"))
      (node (ref "IC6") (pin "7") (pinfunction "VDDCORE_7") (pintype "power_in"))
    )
    (net (code "129") (name "Net-(IC6-~{MCLR})") (class "Default")
      (node (ref "IC6") (pin "18") (pinfunction "~{MCLR}_18") (pintype "bidirectional"))
      (node (ref "JP7") (pin "1") (pinfunction "1_1") (pintype "passive"))
      (node (ref "R54") (pin "1") (pinfunction "1_1") (pintype "passive"))
    )
    (net (code "130") (name "Net-(J1-Pad1)") (class "Default")
      (node (ref "J1") (pin "1") (pinfunction "1_1") (pintype "passive"))
      (node (ref "J1") (pin "2") (pinfunction "2_2") (pintype "passive"))
      (node (ref "U$15") (pin "2") (pinfunction "2_2") (pintype "bidirectional"))
      (node (ref "U$16") (pin "1") (pinfunction "1_1") (pintype "bidirectional"))
      (node (ref "U$16") (pin "4") (pinfunction "4_4") (pintype "bidirectional"))
    )
    (net (code "131") (name "Net-(JP2-Pad2)") (class "Default")
      (node (ref "JP2") (pin "2") (pinfunction "2_2") (pintype "passive"))
      (node (ref "R9") (pin "2") (pinfunction "2_2") (pintype "passive"))
    )
    (net (code "132") (name "Net-(JP3-Pad2)") (class "Default")
      (node (ref "JP3") (pin "2") (pinfunction "2_2") (pintype "passive"))
      (node (ref "R10") (pin "1") (pinfunction "1_1") (pintype "passive"))
    )
    (net (code "133") (name "Net-(JP4-Pad3)") (class "Default")
      (node (ref "JP4") (pin "3") (pinfunction "3_3") (pintype "passive"))
      (node (ref "JP5") (pin "1") (pinfunction "1_1") (pintype "passive"))
    )
    (net (code "134") (name "Net-(JP4-Pad4)") (class "Default")
      (node (ref "JP4") (pin "4") (pinfunction "4_4") (pintype "passive"))
      (node (ref "JP5") (pin "2") (pinfunction "2_2") (pintype "passive"))
    )
    (net (code "135") (name "Net-(JP9-Pad1)") (class "Default")
      (node (ref "JP9") (pin "1") (pinfunction "1_1") (pintype "passive"))
      (node (ref "R12") (pin "1") (pinfunction "1_1") (pintype "passive"))
    )
    (net (code "136") (name "Net-(LED1-PadC)") (class "Default")
      (node (ref "LED1") (pin "C") (pinfunction "C_C") (pintype "passive"))
      (node (ref "R25") (pin "2") (pinfunction "2_2") (pintype "passive"))
    )
    (net (code "137") (name "Net-(LED2-PadC)") (class "Default")
      (node (ref "LED2") (pin "C") (pinfunction "C_C") (pintype "passive"))
      (node (ref "R26") (pin "2") (pinfunction "2_2") (pintype "passive"))
    )
    (net (code "138") (name "Net-(LED3-PadC)") (class "Default")
      (node (ref "LED3") (pin "C") (pinfunction "C_C") (pintype "passive"))
      (node (ref "R27") (pin "2") (pinfunction "2_2") (pintype "passive"))
    )
    (net (code "139") (name "Net-(LED4-PadC)") (class "Default")
      (node (ref "LED4") (pin "C") (pinfunction "C_C") (pintype "passive"))
      (node (ref "R28") (pin "2") (pinfunction "2_2") (pintype "passive"))
    )
    (net (code "140") (name "Net-(LED5-PadC)") (class "Default")
      (node (ref "LED5") (pin "C") (pinfunction "C_C") (pintype "passive"))
      (node (ref "R11") (pin "2") (pinfunction "2_2") (pintype "passive"))
    )
    (net (code "141") (name "Net-(LED9-PadC)") (class "Default")
      (node (ref "LED9") (pin "C") (pinfunction "C_C") (pintype "passive"))
      (node (ref "R34") (pin "2") (pinfunction "2_2") (pintype "passive"))
    )
    (net (code "142") (name "Net-(LED10-PadC)") (class "Default")
      (node (ref "LED10") (pin "C") (pinfunction "C_C") (pintype "passive"))
      (node (ref "R49") (pin "2") (pinfunction "2_2") (pintype "passive"))
    )
    (net (code "143") (name "Net-(LED11-PadC)") (class "Default")
      (node (ref "LED11") (pin "C") (pinfunction "C_C") (pintype "passive"))
      (node (ref "R50") (pin "2") (pinfunction "2_2") (pintype "passive"))
    )
    (net (code "144") (name "Net-(LED12-PadC)") (class "Default")
      (node (ref "LED12") (pin "C") (pinfunction "C_C") (pintype "passive"))
      (node (ref "R52") (pin "2") (pinfunction "2_2") (pintype "passive"))
    )
    (net (code "145") (name "Net-(LED13-PadC)") (class "Default")
      (node (ref "LED13") (pin "C") (pinfunction "C_C") (pintype "passive"))
      (node (ref "R53") (pin "2") (pinfunction "2_2") (pintype "passive"))
    )
    (net (code "146") (name "Net-(LED14-PadC)") (class "Default")
      (node (ref "LED14") (pin "C") (pinfunction "C_C") (pintype "passive"))
      (node (ref "R7") (pin "2") (pinfunction "2_2") (pintype "passive"))
    )
    (net (code "147") (name "Net-(Q1-D)") (class "Default")
      (node (ref "Q1") (pin "3") (pinfunction "D_3") (pintype "bidirectional"))
      (node (ref "R22") (pin "1") (pinfunction "1_1") (pintype "passive"))
    )
    (net (code "148") (name "Net-(Q2-D)") (class "Default")
      (node (ref "Q2") (pin "3") (pinfunction "D_3") (pintype "bidirectional"))
      (node (ref "R23") (pin "1") (pinfunction "1_1") (pintype "passive"))
    )
    (net (code "149") (name "Net-(Q3-D)") (class "Default")
      (node (ref "Q3") (pin "3") (pinfunction "D_3") (pintype "bidirectional"))
      (node (ref "R24") (pin "1") (pinfunction "1_1") (pintype "passive"))
    )
    (net (code "150") (name "Net-(Q4-D)") (class "Default")
      (node (ref "Q4") (pin "3") (pinfunction "D_3") (pintype "bidirectional"))
      (node (ref "SG2") (pin "1") (pinfunction "1_1") (pintype "passive"))
    )
    (net (code "151") (name "Net-(R6-Pad1)") (class "Default")
      (node (ref "R6") (pin "1") (pinfunction "1_1") (pintype "passive"))
      (node (ref "U$82") (pin "3") (pinfunction "3_3") (pintype "bidirectional"))
      (node (ref "U$82") (pin "6") (pinfunction "6_6") (pintype "bidirectional"))
    )
    (net (code "152") (name "Net-(R42-Pad1)") (class "Default")
      (node (ref "R42") (pin "1") (pinfunction "1_1") (pintype "passive"))
      (node (ref "SJ1") (pin "2") (pinfunction "2_2") (pintype "passive"))
    )
    (net (code "153") (name "Net-(R43-Pad1)") (class "Default")
      (node (ref "R43") (pin "1") (pinfunction "1_1") (pintype "passive"))
      (node (ref "SJ2") (pin "2") (pinfunction "2_2") (pintype "passive"))
    )
    (net (code "154") (name "Net-(U$1-P35{slash}NMI)") (class "Default")
      (node (ref "R1") (pin "2") (pinfunction "2_2") (pintype "passive"))
      (node (ref "U$1") (pin "15") (pinfunction "P35/NMI_15") (pintype "bidirectional"))
    )
    (net (code "155") (name "Net-(U$1-VCL)") (class "Default")
      (node (ref "C1") (pin "1") (pinfunction "1_1") (pintype "passive"))
      (node (ref "U$1") (pin "5") (pinfunction "VCL_5") (pintype "bidirectional"))
    )
    (net (code "156") (name "Net-(U$12-UART_CTS)") (class "Default")
      (node (ref "U$12") (pin "15") (pinfunction "UART_RTS_15") (pintype "bidirectional"))
      (node (ref "U$12") (pin "16") (pinfunction "UART_CTS_16") (pintype "bidirectional"))
    )
    (net (code "157") (name "Net-(U$22-D+)") (class "Default")
      (node (ref "R44") (pin "1") (pinfunction "1_1") (pintype "passive"))
      (node (ref "U$22") (pin "3") (pinfunction "D+_3") (pintype "bidirectional"))
    )
    (net (code "158") (name "Net-(U$22-D-)") (class "Default")
      (node (ref "R45") (pin "1") (pinfunction "1_1") (pintype "passive"))
      (node (ref "U$22") (pin "2") (pinfunction "D-_2") (pintype "bidirectional"))
    )
    (net (code "159") (name "Net-(U$22-VCC)") (class "Default")
      (node (ref "R46") (pin "1") (pinfunction "1_1") (pintype "passive"))
      (node (ref "U$22") (pin "1") (pinfunction "VCC_1") (pintype "power_in"))
    )
    (net (code "160") (name "Net-(U$58-BLUE)") (class "Default")
      (node (ref "R22") (pin "2") (pinfunction "2_2") (pintype "passive"))
      (node (ref "U$58") (pin "4") (pinfunction "BLUE_4") (pintype "bidirectional"))
    )
    (net (code "161") (name "Net-(U$58-GREEN)") (class "Default")
      (node (ref "R23") (pin "2") (pinfunction "2_2") (pintype "passive"))
      (node (ref "U$58") (pin "2") (pinfunction "GREEN_2") (pintype "bidirectional"))
    )
    (net (code "162") (name "Net-(U$58-RED)") (class "Default")
      (node (ref "R24") (pin "2") (pinfunction "2_2") (pintype "passive"))
      (node (ref "U$58") (pin "1") (pinfunction "RED_1") (pintype "bidirectional"))
    )
    (net (code "163") (name "Net-(U$76-Pad1)") (class "Default")
      (node (ref "U$76") (pin "1") (pinfunction "1_1") (pintype "passive"))
      (node (ref "X3") (pin "1") (pinfunction "1_1") (pintype "passive"))
    )
    (net (code "164") (name "unconnected-(FT231XS-CBUS0-Pad18)") (class "Default")
      (node (ref "FT231XS") (pin "18") (pinfunction "CBUS0_18") (pintype "bidirectional"))
    )
    (net (code "165") (name "unconnected-(FT231XS-CBUS1-Pad17)") (class "Default")
      (node (ref "FT231XS") (pin "17") (pinfunction "CBUS1_17") (pintype "bidirectional"))
    )
    (net (code "166") (name "unconnected-(FT231XS-CBUS2-Pad10)") (class "Default")
      (node (ref "FT231XS") (pin "10") (pinfunction "CBUS2_10") (pintype "bidirectional"))
    )
    (net (code "167") (name "unconnected-(FT231XS-CBUS3-Pad19)") (class "Default")
      (node (ref "FT231XS") (pin "19") (pinfunction "CBUS3_19") (pintype "bidirectional"))
    )
    (net (code "168") (name "unconnected-(FT231XS-CTS#-Pad9)") (class "Default")
      (node (ref "FT231XS") (pin "9") (pinfunction "CTS#_9") (pintype "bidirectional"))
    )
    (net (code "169") (name "unconnected-(FT231XS-DCD#-Pad8)") (class "Default")
      (node (ref "FT231XS") (pin "8") (pinfunction "DCD#_8") (pintype "bidirectional"))
    )
    (net (code "170") (name "unconnected-(FT231XS-DSR#-Pad7)") (class "Default")
      (node (ref "FT231XS") (pin "7") (pinfunction "DSR#_7") (pintype "bidirectional"))
    )
    (net (code "171") (name "unconnected-(FT231XS-DTR#-Pad1)") (class "Default")
      (node (ref "FT231XS") (pin "1") (pinfunction "DTR#_1") (pintype "bidirectional"))
    )
    (net (code "172") (name "unconnected-(FT231XS-RI#-Pad5)") (class "Default")
      (node (ref "FT231XS") (pin "5") (pinfunction "RI#_5") (pintype "bidirectional"))
    )
    (net (code "173") (name "unconnected-(FT231XS-RTS#-Pad2)") (class "Default")
      (node (ref "FT231XS") (pin "2") (pinfunction "RTS#_2") (pintype "bidirectional"))
    )
    (net (code "174") (name "unconnected-(IC6-RA0-Pad19)") (class "Default")
      (node (ref "IC6") (pin "19") (pinfunction "RA0_19") (pintype "bidirectional"))
    )
    (net (code "175") (name "unconnected-(IC6-RA1-Pad20)") (class "Default")
      (node (ref "IC6") (pin "20") (pinfunction "RA1_20") (pintype "bidirectional"))
    )
    (net (code "176") (name "unconnected-(IC6-RA2-Pad30)") (class "Default")
      (node (ref "IC6") (pin "30") (pinfunction "RA2_30") (pintype "bidirectional"))
    )
    (net (code "177") (name "unconnected-(IC6-RA3-Pad31)") (class "Default")
      (node (ref "IC6") (pin "31") (pinfunction "RA3_31") (pintype "bidirectional"))
    )
    (net (code "178") (name "unconnected-(IC6-RA4-Pad34)") (class "Default")
      (node (ref "IC6") (pin "34") (pinfunction "RA4_34") (pintype "bidirectional"))
    )
    (net (code "179") (name "unconnected-(IC6-RB2-Pad23)") (class "Default")
      (node (ref "IC6") (pin "23") (pinfunction "RB2_23") (pintype "bidirectional"))
    )
    (net (code "180") (name "unconnected-(IC6-RB3-Pad24)") (class "Default")
      (node (ref "IC6") (pin "24") (pinfunction "RB3_24") (pintype "bidirectional"))
    )
    (net (code "181") (name "unconnected-(IC6-RB4-Pad33)") (class "Default")
      (node (ref "IC6") (pin "33") (pinfunction "RB4_33") (pintype "bidirectional"))
    )
    (net (code "182") (name "unconnected-(IC6-RB13-Pad11)") (class "Default")
      (node (ref "IC6") (pin "11") (pinfunction "RB13_11") (pintype "bidirectional"))
    )
    (net (code "183") (name "unconnected-(IC6-RC0-Pad25)") (class "Default")
      (node (ref "IC6") (pin "25") (pinfunction "RC0_25") (pintype "bidirectional"))
    )
    (net (code "184") (name "unconnected-(IC6-RC1-Pad26)") (class "Default")
      (node (ref "IC6") (pin "26") (pinfunction "RC1_26") (pintype "bidirectional"))
    )
    (net (code "185") (name "unconnected-(IC6-RC2-Pad27)") (class "Default")
      (node (ref "IC6") (pin "27") (pinfunction "RC2_27") (pintype "bidirectional"))
    )
    (net (code "186") (name "unconnected-(IC6-RC3-Pad36)") (class "Default")
      (node (ref "IC6") (pin "36") (pinfunction "RC3_36") (pintype "bidirectional"))
    )
    (net (code "187") (name "unconnected-(IC6-RC4-Pad37)") (class "Default")
      (node (ref "IC6") (pin "37") (pinfunction "RC4_37") (pintype "bidirectional"))
    )
    (net (code "188") (name "unconnected-(IC6-RC5-Pad38)") (class "Default")
      (node (ref "IC6") (pin "38") (pinfunction "RC5_38") (pintype "bidirectional"))
    )
    (net (code "189") (name "unconnected-(IC6-TCK-Pad13)") (class "Default")
      (node (ref "IC6") (pin "13") (pinfunction "TCK_13") (pintype "input"))
    )
    (net (code "190") (name "unconnected-(IC6-TDI-Pad35)") (class "Default")
      (node (ref "IC6") (pin "35") (pinfunction "TDI_35") (pintype "input"))
    )
    (net (code "191") (name "unconnected-(IC6-TDO-Pad32)") (class "Default")
      (node (ref "IC6") (pin "32") (pinfunction "TDO_32") (pintype "output"))
    )
    (net (code "192") (name "unconnected-(IC6-TMS-Pad12)") (class "Default")
      (node (ref "IC6") (pin "12") (pinfunction "TMS_12") (pintype "input"))
    )
    (net (code "193") (name "unconnected-(U$1-PJ3{slash}MITIOC3C-Pad4)") (class "Default")
      (node (ref "U$1") (pin "4") (pinfunction "PJ3/MITIOC3C_4") (pintype "bidirectional"))
    )
    (net (code "194") (name "unconnected-(U$12-AIO0-Pad30)") (class "Default")
      (node (ref "U$12") (pin "30") (pinfunction "AIO0_30") (pintype "bidirectional"))
    )
    (net (code "195") (name "unconnected-(U$12-AIO1-Pad35)") (class "Default")
      (node (ref "U$12") (pin "35") (pinfunction "AIO1_35") (pintype "bidirectional"))
    )
    (net (code "196") (name "unconnected-(U$12-GPIO2-Pad19)") (class "Default")
      (node (ref "U$12") (pin "19") (pinfunction "GPIO2_19") (pintype "bidirectional"))
    )
    (net (code "197") (name "unconnected-(U$12-GPIO3-Pad20)") (class "Default")
      (node (ref "U$12") (pin "20") (pinfunction "GPIO3_20") (pintype "bidirectional"))
    )
    (net (code "198") (name "unconnected-(U$12-GPIO4-Pad21)") (class "Default")
      (node (ref "U$12") (pin "21") (pinfunction "GPIO4_21") (pintype "bidirectional"))
    )
    (net (code "199") (name "unconnected-(U$12-GPIO5-Pad22)") (class "Default")
      (node (ref "U$12") (pin "22") (pinfunction "GPIO5_22") (pintype "bidirectional"))
    )
    (net (code "200") (name "unconnected-(U$12-GPIO6-Pad3)") (class "Default")
      (node (ref "U$12") (pin "3") (pinfunction "GPIO6_3") (pintype "bidirectional"))
    )
    (net (code "201") (name "unconnected-(U$12-GPIO7-Pad4)") (class "Default")
      (node (ref "U$12") (pin "4") (pinfunction "GPIO7_4") (pintype "bidirectional"))
    )
    (net (code "202") (name "unconnected-(U$12-GPIO8-Pad31)") (class "Default")
      (node (ref "U$12") (pin "31") (pinfunction "GPIO8_31") (pintype "bidirectional"))
    )
    (net (code "203") (name "unconnected-(U$12-GPIO9-Pad32)") (class "Default")
      (node (ref "U$12") (pin "32") (pinfunction "GPIO9_32") (pintype "bidirectional"))
    )
    (net (code "204") (name "unconnected-(U$12-GPIO10-Pad33)") (class "Default")
      (node (ref "U$12") (pin "33") (pinfunction "GPIO10_33") (pintype "bidirectional"))
    )
    (net (code "205") (name "unconnected-(U$12-GPIO11-Pad34)") (class "Default")
      (node (ref "U$12") (pin "34") (pinfunction "GPIO11_34") (pintype "bidirectional"))
    )
    (net (code "206") (name "unconnected-(U$12-PCM_CLK-Pad7)") (class "Default")
      (node (ref "U$12") (pin "7") (pinfunction "PCM_CLK_7") (pintype "bidirectional"))
    )
    (net (code "207") (name "unconnected-(U$12-PCM_IN-Pad9)") (class "Default")
      (node (ref "U$12") (pin "9") (pinfunction "PCM_IN_9") (pintype "bidirectional"))
    )
    (net (code "208") (name "unconnected-(U$12-PCM_OUT-Pad10)") (class "Default")
      (node (ref "U$12") (pin "10") (pinfunction "PCM_OUT_10") (pintype "bidirectional"))
    )
    (net (code "209") (name "unconnected-(U$12-PCM_SYNC-Pad8)") (class "Default")
      (node (ref "U$12") (pin "8") (pinfunction "PCM_SYNC_8") (pintype "bidirectional"))
    )
    (net (code "210") (name "unconnected-(U$12-SPI_CLOCK-Pad6)") (class "Default")
      (node (ref "U$12") (pin "6") (pinfunction "SPI_CLOCK_6") (pintype "bidirectional"))
    )
    (net (code "211") (name "unconnected-(U$12-SPI_CSB-Pad23)") (class "Default")
      (node (ref "U$12") (pin "23") (pinfunction "SPI_CSB_23") (pintype "bidirectional"))
    )
    (net (code "212") (name "unconnected-(U$12-SPI_MISO-Pad24)") (class "Default")
      (node (ref "U$12") (pin "24") (pinfunction "SPI_MISO_24") (pintype "bidirectional"))
    )
    (net (code "213") (name "unconnected-(U$12-SPI_MOSI-Pad2)") (class "Default")
      (node (ref "U$12") (pin "2") (pinfunction "SPI_MOSI_2") (pintype "bidirectional"))
    )
    (net (code "214") (name "unconnected-(U$12-USB_D+-Pad17)") (class "Default")
      (node (ref "U$12") (pin "17") (pinfunction "USB_D+_17") (pintype "bidirectional"))
    )
    (net (code "215") (name "unconnected-(U$12-USB_D--Pad18)") (class "Default")
      (node (ref "U$12") (pin "18") (pinfunction "USB_D-_18") (pintype "bidirectional"))
    )
    (net (code "216") (name "unconnected-(U$16-Pad3)") (class "Default")
      (node (ref "U$16") (pin "3") (pinfunction "3_3") (pintype "bidirectional"))
    )
    (net (code "217") (name "unconnected-(U$16-Pad6)") (class "Default")
      (node (ref "U$16") (pin "6") (pinfunction "6_6") (pintype "bidirectional"))
    )
    (net (code "218") (name "unconnected-(U$22-ID-Pad4)") (class "Default")
      (node (ref "U$22") (pin "4") (pinfunction "ID_4") (pintype "bidirectional"))
    )
    (net (code "219") (name "unconnected-(X1K-S-Pad6)") (class "Default")
      (node (ref "X1") (pin "6") (pinfunction "S_6") (pintype "passive"))
    )
  )
)
